# seamonster_buffered3.net
KiCad netlist of a schematic drawn in EAGLE
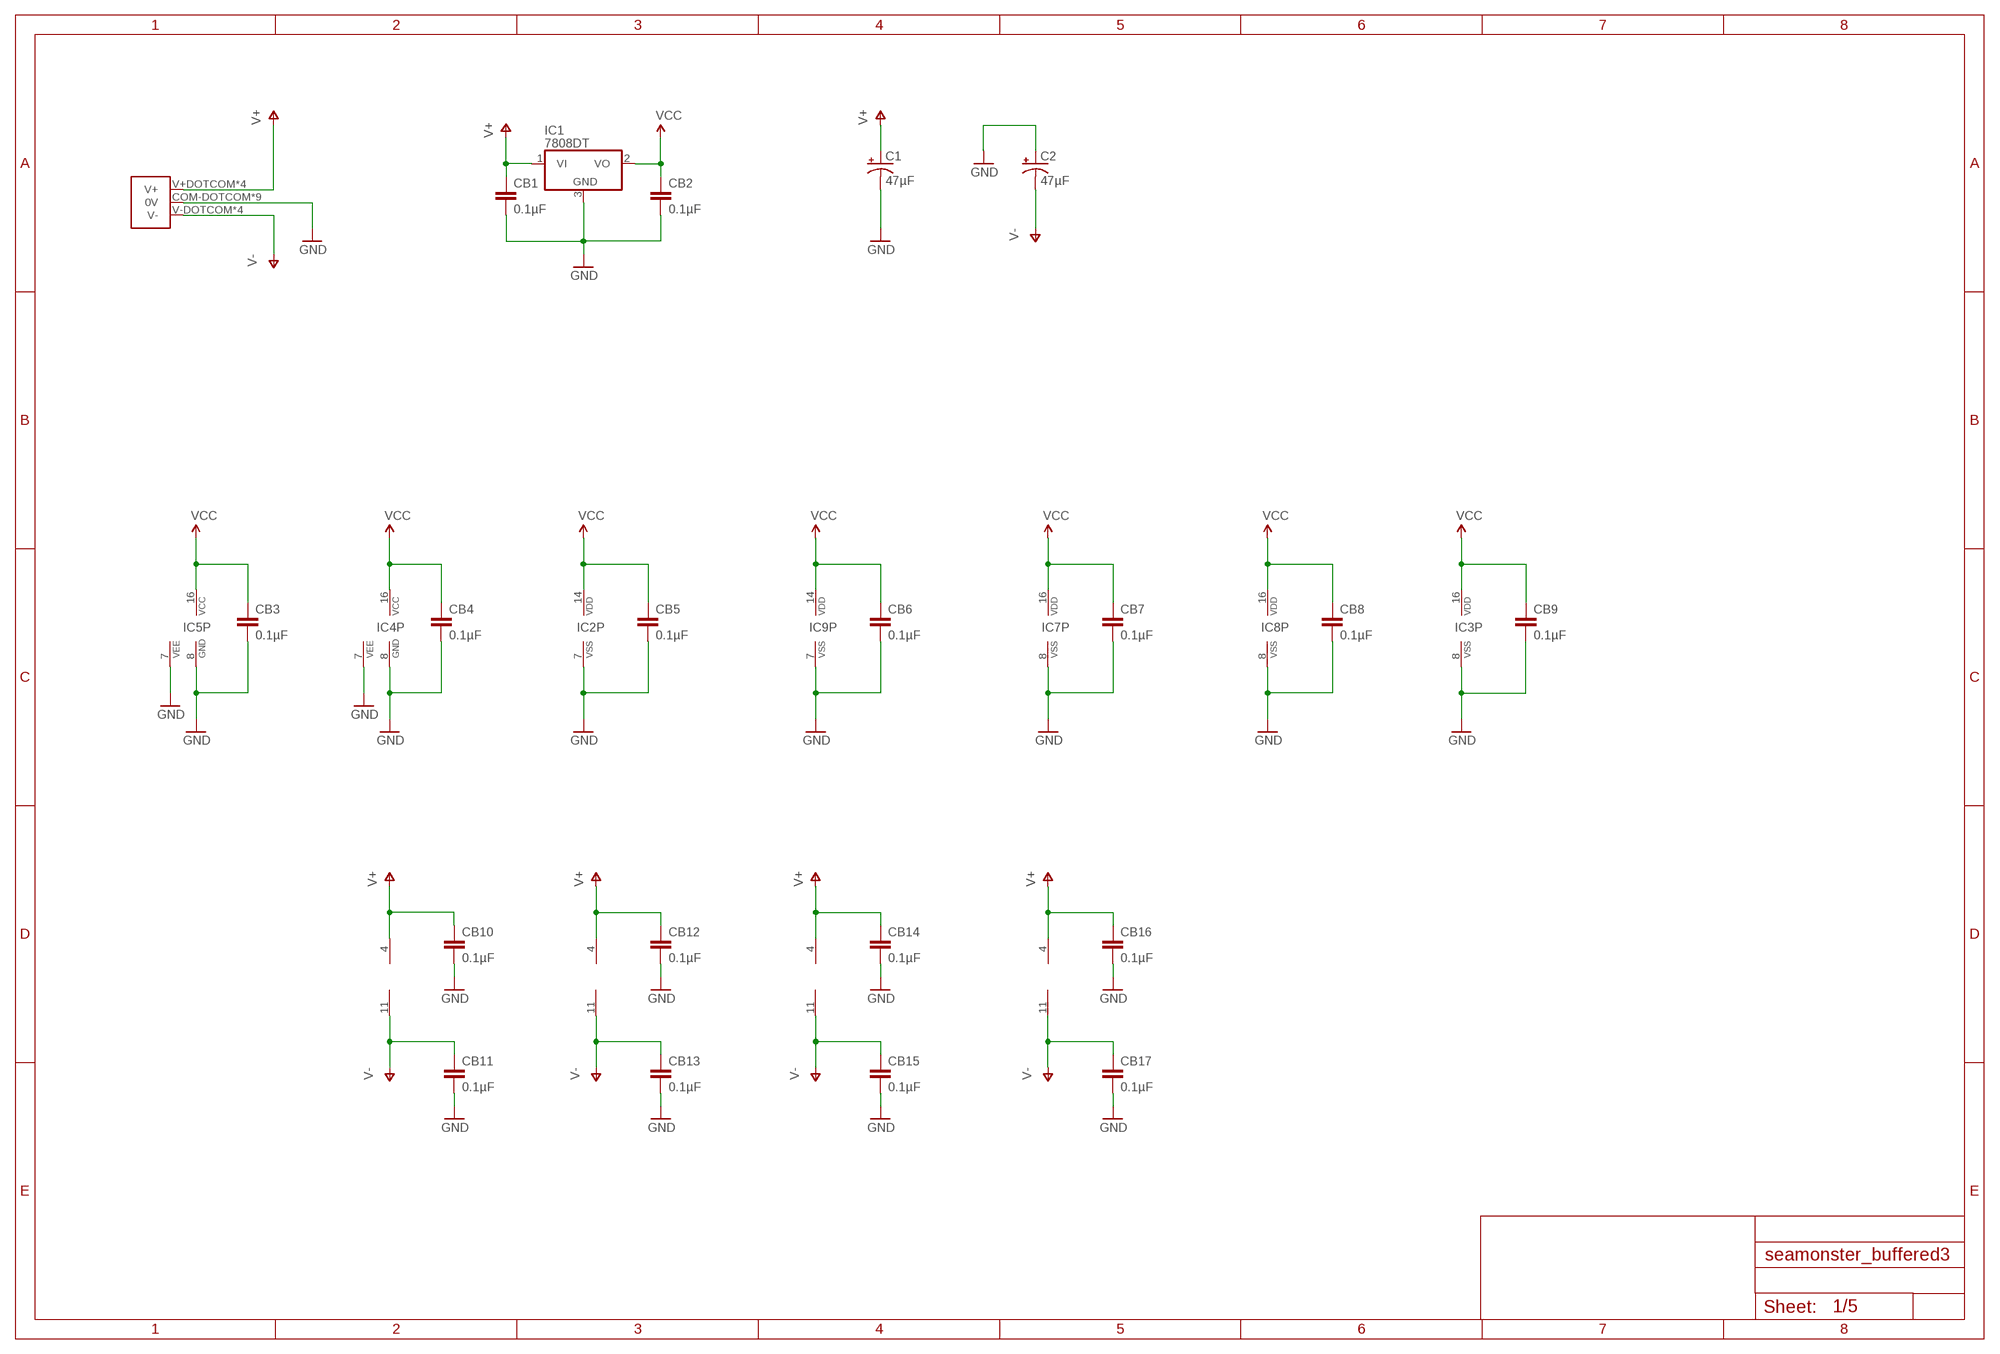
[diagram p0: schematic, sheet 1]
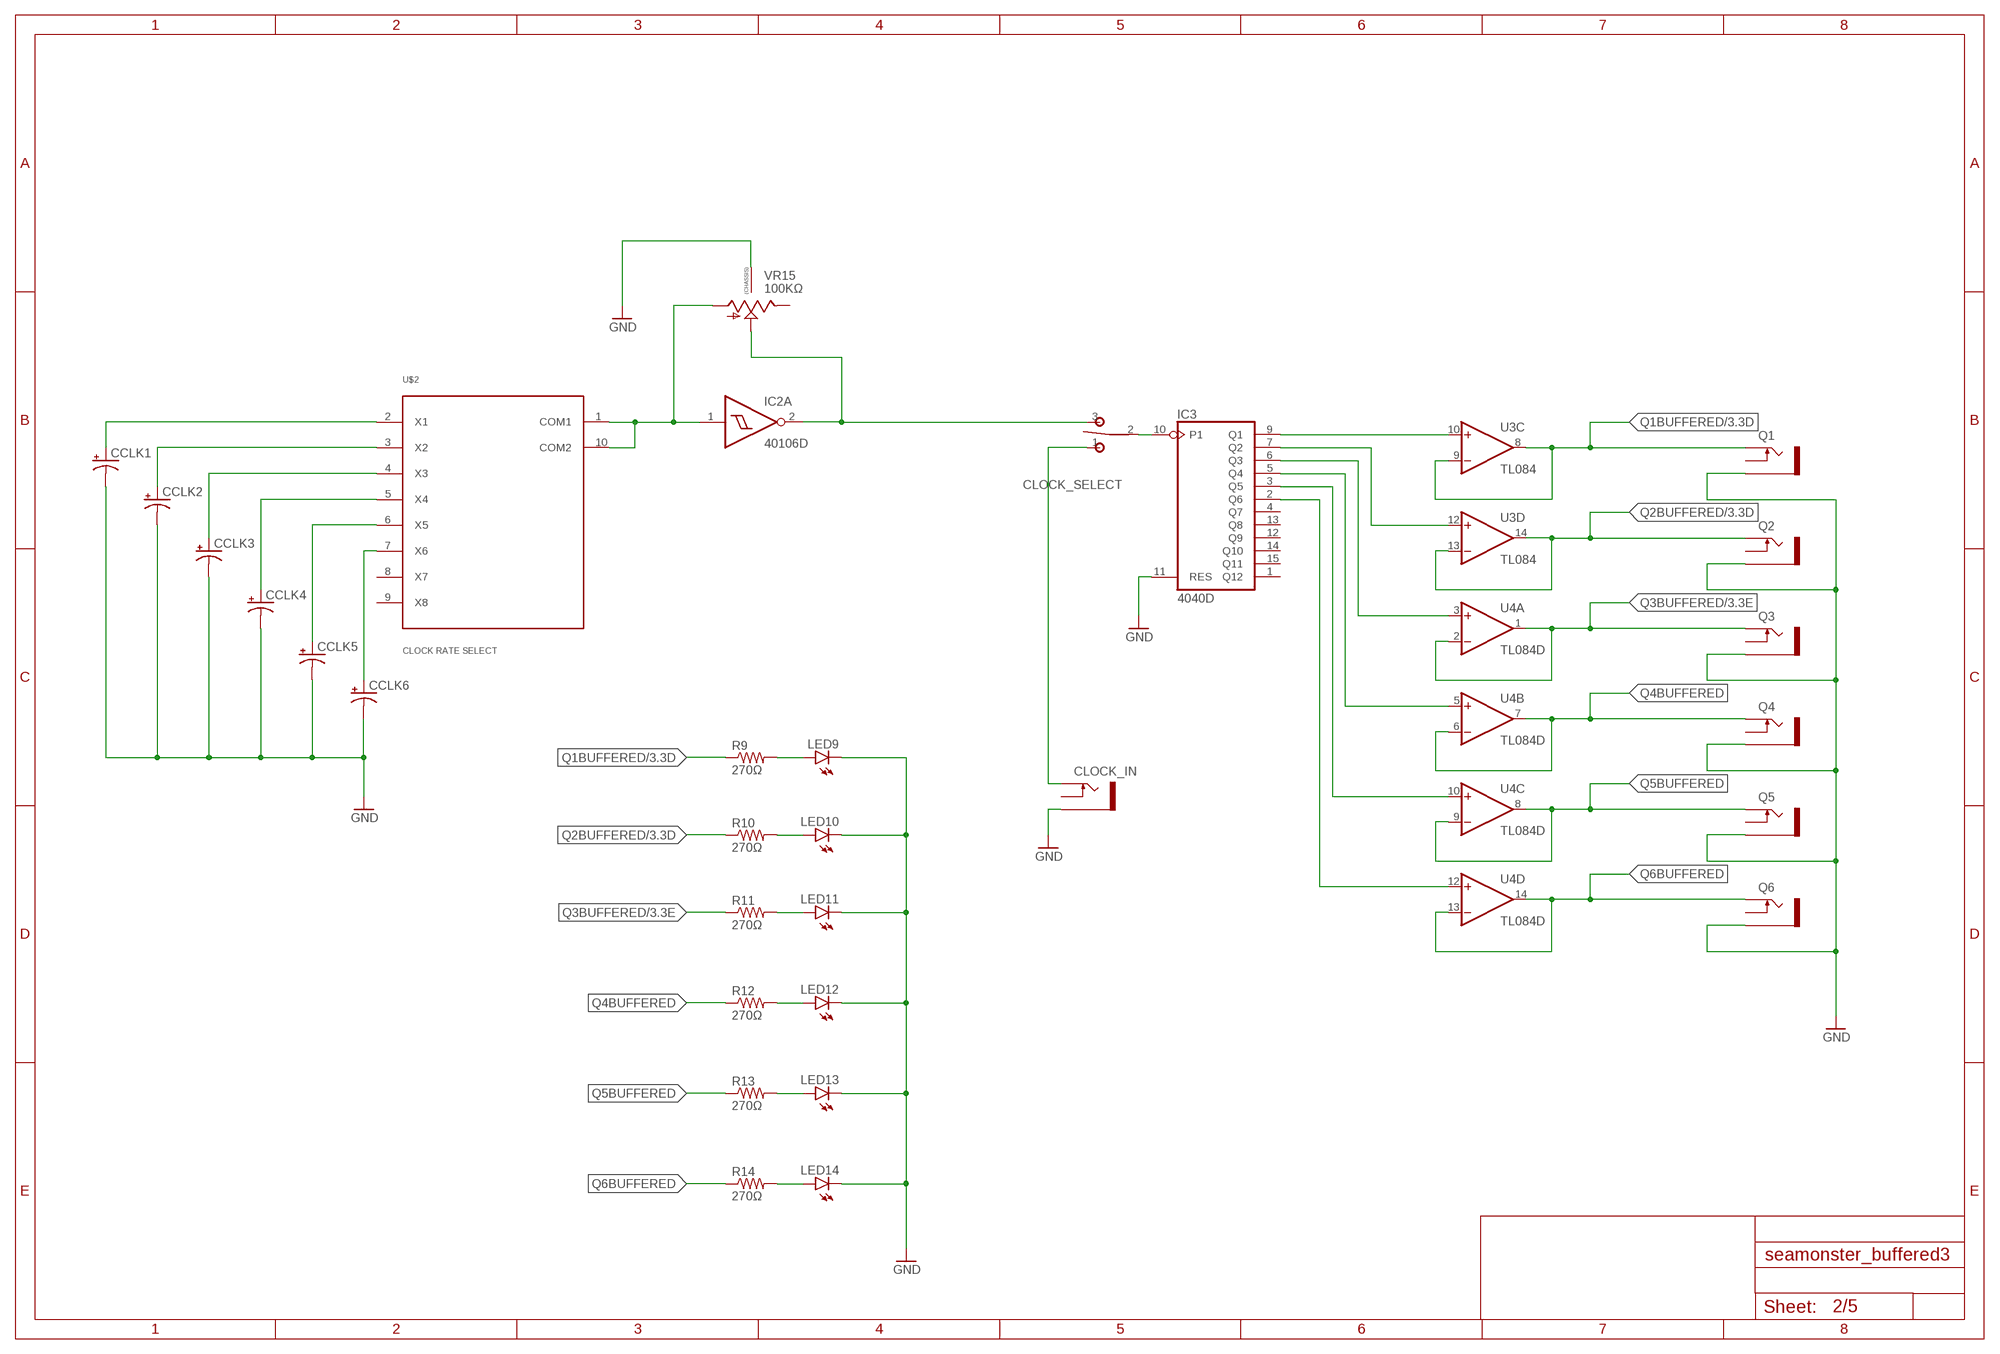
[diagram p1: schematic, sheet 2]
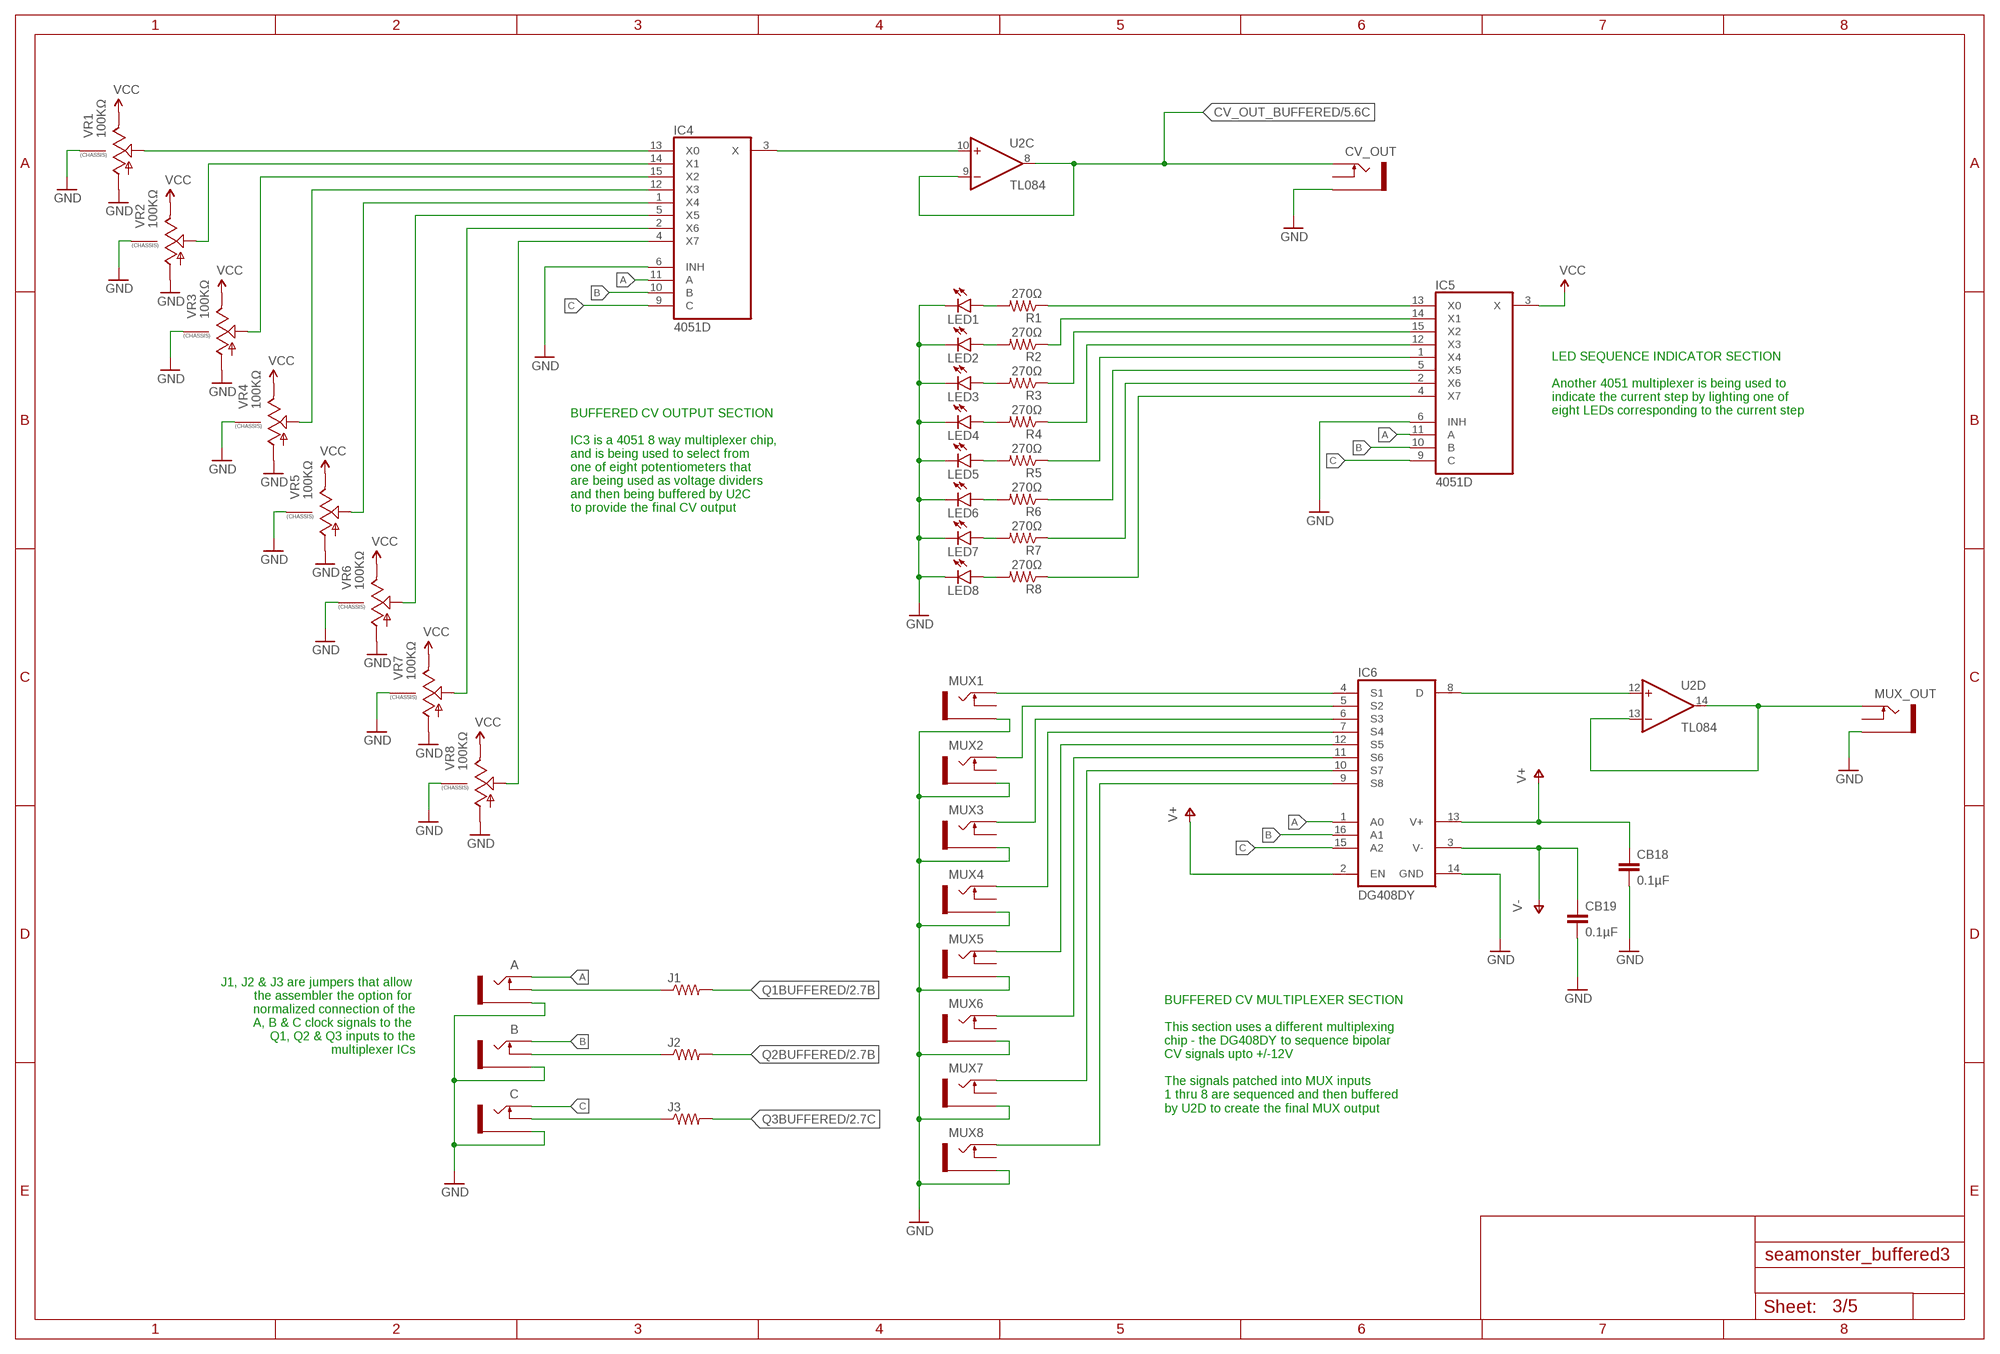
[diagram p2: schematic, sheet 3]
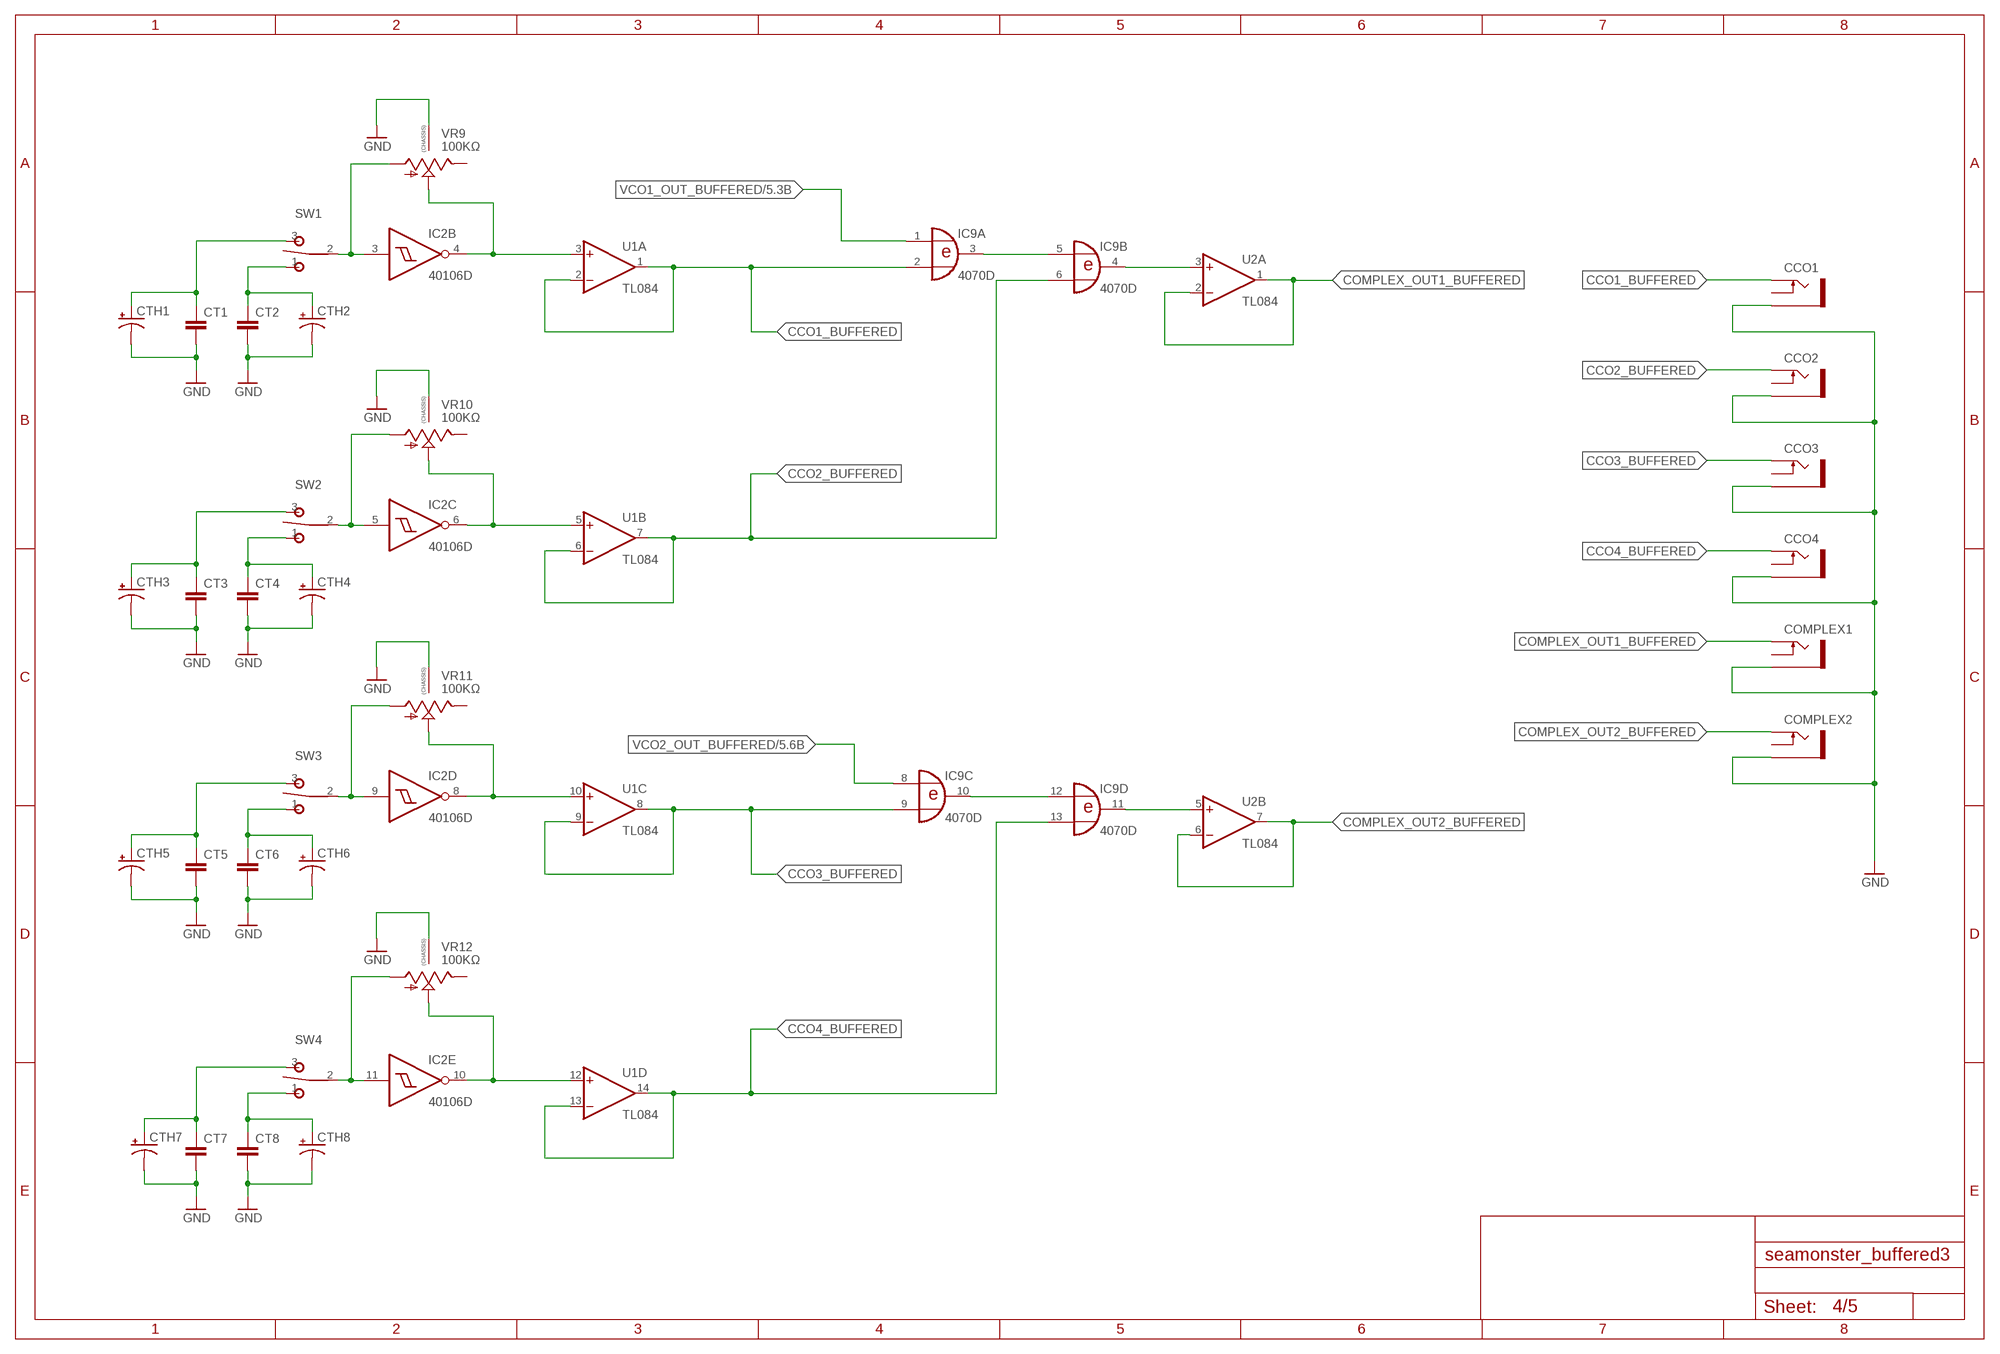
[diagram p3: schematic, sheet 4]
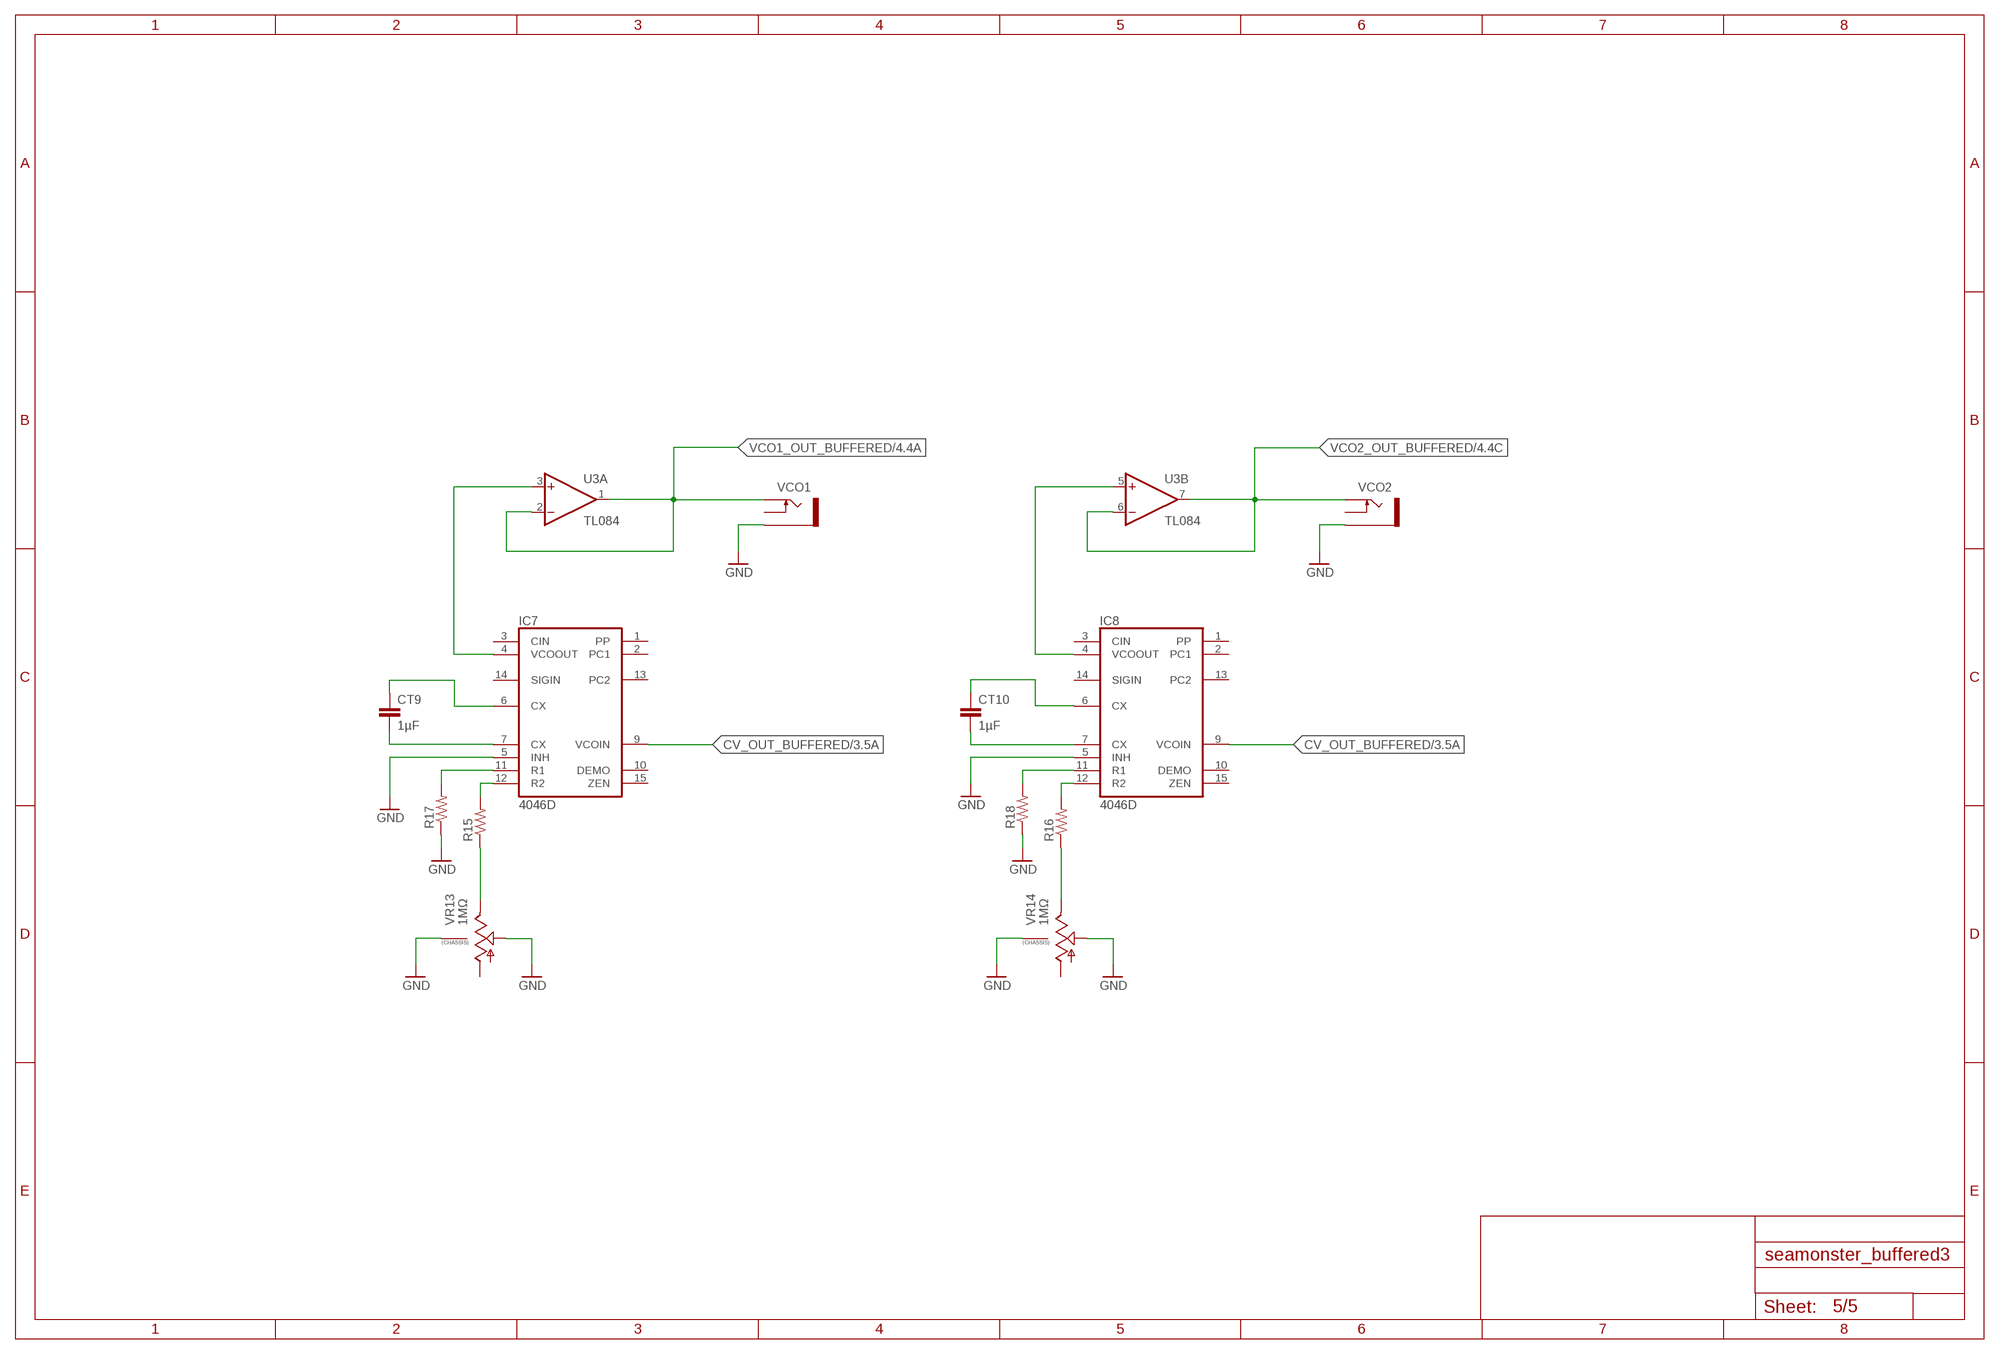
[diagram p4: schematic, sheet 5]

(export (version "E")
  (design (tool "Eeschema 10.0.6"))
  (components
    (comp (ref "A")
      (value "THONKICONNNEW")
      (footprint "eagle-import:WQP-PJ301M-12_JACK")
      (libsource (lib "eagle-import") (part "THONKICONNNEW"))
    )
    (comp (ref "B")
      (value "THONKICONNNEW")
      (footprint "eagle-import:WQP-PJ301M-12_JACK")
      (libsource (lib "eagle-import") (part "THONKICONNNEW"))
    )
    (comp (ref "C")
      (value "THONKICONNNEW")
      (footprint "eagle-import:WQP-PJ301M-12_JACK")
      (libsource (lib "eagle-import") (part "THONKICONNNEW"))
    )
    (comp (ref "CB18")
      (value "0.1µF")
      (footprint "eagle-import:0805")
      (libsource (lib "eagle-import") (part "CAP0805"))
    )
    (comp (ref "CB19")
      (value "0.1µF")
      (footprint "eagle-import:0805")
      (libsource (lib "eagle-import") (part "CAP0805"))
    )
    (comp (ref "CV_OUT")
      (value "THONKICONNNEW")
      (footprint "eagle-import:WQP-PJ301M-12_JACK")
      (libsource (lib "eagle-import") (part "THONKICONNNEW"))
    )
    (comp (ref "IC4")
      (value "4051D")
      (footprint "eagle-import:SO16")
      (libsource (lib "eagle-import") (part "4051D"))
    )
    (comp (ref "IC5")
      (value "4051D")
      (footprint "eagle-import:SO16")
      (libsource (lib "eagle-import") (part "4051D"))
    )
    (comp (ref "IC6")
      (value "DG408DY")
      (footprint "eagle-import:SO16")
      (fields (field (name "MPN") "DG408DY+T"))
      (libsource (lib "eagle-import") (part "DG408DY"))
    )
    (comp (ref "J1")
      (value "RESISTOR0805-RES")
      (footprint "eagle-import:0805")
      (libsource (lib "eagle-import") (part "RESISTOR0805-RES"))
    )
    (comp (ref "J2")
      (value "RESISTOR0805-RES")
      (footprint "eagle-import:0805")
      (libsource (lib "eagle-import") (part "RESISTOR0805-RES"))
    )
    (comp (ref "J3")
      (value "RESISTOR0805-RES")
      (footprint "eagle-import:0805")
      (libsource (lib "eagle-import") (part "RESISTOR0805-RES"))
    )
    (comp (ref "LED1")
      (value "LED3MM")
      (footprint "eagle-import:LED3MM")
      (libsource (lib "eagle-import") (part "LED3MM"))
    )
    (comp (ref "LED2")
      (value "LED3MM")
      (footprint "eagle-import:LED3MM")
      (libsource (lib "eagle-import") (part "LED3MM"))
    )
    (comp (ref "LED3")
      (value "LED3MM")
      (footprint "eagle-import:LED3MM")
      (libsource (lib "eagle-import") (part "LED3MM"))
    )
    (comp (ref "LED4")
      (value "LED3MM")
      (footprint "eagle-import:LED3MM")
      (libsource (lib "eagle-import") (part "LED3MM"))
    )
    (comp (ref "LED5")
      (value "LED3MM")
      (footprint "eagle-import:LED3MM")
      (libsource (lib "eagle-import") (part "LED3MM"))
    )
    (comp (ref "LED6")
      (value "LED3MM")
      (footprint "eagle-import:LED3MM")
      (libsource (lib "eagle-import") (part "LED3MM"))
    )
    (comp (ref "LED7")
      (value "LED3MM")
      (footprint "eagle-import:LED3MM")
      (libsource (lib "eagle-import") (part "LED3MM"))
    )
    (comp (ref "LED8")
      (value "LED3MM")
      (footprint "eagle-import:LED3MM")
      (libsource (lib "eagle-import") (part "LED3MM"))
    )
    (comp (ref "MUX1")
      (value "THONKICONNNEW")
      (footprint "eagle-import:WQP-PJ301M-12_JACK")
      (libsource (lib "eagle-import") (part "THONKICONNNEW"))
    )
    (comp (ref "MUX2")
      (value "THONKICONNNEW")
      (footprint "eagle-import:WQP-PJ301M-12_JACK")
      (libsource (lib "eagle-import") (part "THONKICONNNEW"))
    )
    (comp (ref "MUX3")
      (value "THONKICONNNEW")
      (footprint "eagle-import:WQP-PJ301M-12_JACK")
      (libsource (lib "eagle-import") (part "THONKICONNNEW"))
    )
    (comp (ref "MUX4")
      (value "THONKICONNNEW")
      (footprint "eagle-import:WQP-PJ301M-12_JACK")
      (libsource (lib "eagle-import") (part "THONKICONNNEW"))
    )
    (comp (ref "MUX5")
      (value "THONKICONNNEW")
      (footprint "eagle-import:WQP-PJ301M-12_JACK")
      (libsource (lib "eagle-import") (part "THONKICONNNEW"))
    )
    (comp (ref "MUX6")
      (value "THONKICONNNEW")
      (footprint "eagle-import:WQP-PJ301M-12_JACK")
      (libsource (lib "eagle-import") (part "THONKICONNNEW"))
    )
    (comp (ref "MUX7")
      (value "THONKICONNNEW")
      (footprint "eagle-import:WQP-PJ301M-12_JACK")
      (libsource (lib "eagle-import") (part "THONKICONNNEW"))
    )
    (comp (ref "MUX8")
      (value "THONKICONNNEW")
      (footprint "eagle-import:WQP-PJ301M-12_JACK")
      (libsource (lib "eagle-import") (part "THONKICONNNEW"))
    )
    (comp (ref "MUX_OUT")
      (value "THONKICONNNEW")
      (footprint "eagle-import:WQP-PJ301M-12_JACK")
      (libsource (lib "eagle-import") (part "THONKICONNNEW"))
    )
    (comp (ref "R1")
      (value "270Ω")
      (footprint "eagle-import:0805")
      (libsource (lib "eagle-import") (part "RESISTOR0805-RES"))
    )
    (comp (ref "R2")
      (value "270Ω")
      (footprint "eagle-import:0805")
      (libsource (lib "eagle-import") (part "RESISTOR0805-RES"))
    )
    (comp (ref "R3")
      (value "270Ω")
      (footprint "eagle-import:0805")
      (libsource (lib "eagle-import") (part "RESISTOR0805-RES"))
    )
    (comp (ref "R4")
      (value "270Ω")
      (footprint "eagle-import:0805")
      (libsource (lib "eagle-import") (part "RESISTOR0805-RES"))
    )
    (comp (ref "R5")
      (value "270Ω")
      (footprint "eagle-import:0805")
      (libsource (lib "eagle-import") (part "RESISTOR0805-RES"))
    )
    (comp (ref "R6")
      (value "270Ω")
      (footprint "eagle-import:0805")
      (libsource (lib "eagle-import") (part "RESISTOR0805-RES"))
    )
    (comp (ref "R7")
      (value "270Ω")
      (footprint "eagle-import:0805")
      (libsource (lib "eagle-import") (part "RESISTOR0805-RES"))
    )
    (comp (ref "R8")
      (value "270Ω")
      (footprint "eagle-import:0805")
      (libsource (lib "eagle-import") (part "RESISTOR0805-RES"))
    )
    (comp (ref "U2")
      (value "TL084")
      (footprint "eagle-import:SO14")
      (libsource (lib "eagle-import") (part "TL074_SMD"))
    )
    (comp (ref "VR1")
      (value "100KΩ")
      (footprint "eagle-import:9MM_SNAP-IN_POT")
      (libsource (lib "eagle-import") (part "9MM_SNAP-IN_POT_CHASSIS"))
    )
    (comp (ref "VR2")
      (value "100KΩ")
      (footprint "eagle-import:9MM_SNAP-IN_POT")
      (libsource (lib "eagle-import") (part "9MM_SNAP-IN_POT_CHASSIS"))
    )
    (comp (ref "VR3")
      (value "100KΩ")
      (footprint "eagle-import:9MM_SNAP-IN_POT")
      (libsource (lib "eagle-import") (part "9MM_SNAP-IN_POT_CHASSIS"))
    )
    (comp (ref "VR4")
      (value "100KΩ")
      (footprint "eagle-import:9MM_SNAP-IN_POT")
      (libsource (lib "eagle-import") (part "9MM_SNAP-IN_POT_CHASSIS"))
    )
    (comp (ref "VR5")
      (value "100KΩ")
      (footprint "eagle-import:9MM_SNAP-IN_POT")
      (libsource (lib "eagle-import") (part "9MM_SNAP-IN_POT_CHASSIS"))
    )
    (comp (ref "VR6")
      (value "100KΩ")
      (footprint "eagle-import:9MM_SNAP-IN_POT")
      (libsource (lib "eagle-import") (part "9MM_SNAP-IN_POT_CHASSIS"))
    )
    (comp (ref "VR7")
      (value "100KΩ")
      (footprint "eagle-import:9MM_SNAP-IN_POT")
      (libsource (lib "eagle-import") (part "9MM_SNAP-IN_POT_CHASSIS"))
    )
    (comp (ref "VR8")
      (value "100KΩ")
      (footprint "eagle-import:9MM_SNAP-IN_POT")
      (libsource (lib "eagle-import") (part "9MM_SNAP-IN_POT_CHASSIS"))
    )
    (comp (ref "CCO1")
      (value "THONKICONNNEW")
      (footprint "eagle-import:WQP-PJ301M-12_JACK")
      (libsource (lib "eagle-import") (part "THONKICONNNEW"))
    )
    (comp (ref "CCO2")
      (value "THONKICONNNEW")
      (footprint "eagle-import:WQP-PJ301M-12_JACK")
      (libsource (lib "eagle-import") (part "THONKICONNNEW"))
    )
    (comp (ref "CCO3")
      (value "THONKICONNNEW")
      (footprint "eagle-import:WQP-PJ301M-12_JACK")
      (libsource (lib "eagle-import") (part "THONKICONNNEW"))
    )
    (comp (ref "CCO4")
      (value "THONKICONNNEW")
      (footprint "eagle-import:WQP-PJ301M-12_JACK")
      (libsource (lib "eagle-import") (part "THONKICONNNEW"))
    )
    (comp (ref "COMPLEX1")
      (value "THONKICONNNEW")
      (footprint "eagle-import:WQP-PJ301M-12_JACK")
      (libsource (lib "eagle-import") (part "THONKICONNNEW"))
    )
    (comp (ref "COMPLEX2")
      (value "THONKICONNNEW")
      (footprint "eagle-import:WQP-PJ301M-12_JACK")
      (libsource (lib "eagle-import") (part "THONKICONNNEW"))
    )
    (comp (ref "CT1")
      (value "CAP0805")
      (footprint "eagle-import:0805")
      (libsource (lib "eagle-import") (part "CAP0805"))
    )
    (comp (ref "CT2")
      (value "CAP0805")
      (footprint "eagle-import:0805")
      (libsource (lib "eagle-import") (part "CAP0805"))
    )
    (comp (ref "CT3")
      (value "CAP0805")
      (footprint "eagle-import:0805")
      (libsource (lib "eagle-import") (part "CAP0805"))
    )
    (comp (ref "CT4")
      (value "CAP0805")
      (footprint "eagle-import:0805")
      (libsource (lib "eagle-import") (part "CAP0805"))
    )
    (comp (ref "CT5")
      (value "CAP0805")
      (footprint "eagle-import:0805")
      (libsource (lib "eagle-import") (part "CAP0805"))
    )
    (comp (ref "CT6")
      (value "CAP0805")
      (footprint "eagle-import:0805")
      (libsource (lib "eagle-import") (part "CAP0805"))
    )
    (comp (ref "CT7")
      (value "CAP0805")
      (footprint "eagle-import:0805")
      (libsource (lib "eagle-import") (part "CAP0805"))
    )
    (comp (ref "CT8")
      (value "CAP0805")
      (footprint "eagle-import:0805")
      (libsource (lib "eagle-import") (part "CAP0805"))
    )
    (comp (ref "CTH1")
      (value "CAP_POLPTH2")
      (footprint "eagle-import:CPOL-RADIAL-10UF-25V")
      (libsource (lib "eagle-import") (part "CAP_POLPTH2"))
    )
    (comp (ref "CTH2")
      (value "CAP_POLPTH2")
      (footprint "eagle-import:CPOL-RADIAL-10UF-25V")
      (libsource (lib "eagle-import") (part "CAP_POLPTH2"))
    )
    (comp (ref "CTH3")
      (value "CAP_POLPTH2")
      (footprint "eagle-import:CPOL-RADIAL-10UF-25V")
      (libsource (lib "eagle-import") (part "CAP_POLPTH2"))
    )
    (comp (ref "CTH4")
      (value "CAP_POLPTH2")
      (footprint "eagle-import:CPOL-RADIAL-10UF-25V")
      (libsource (lib "eagle-import") (part "CAP_POLPTH2"))
    )
    (comp (ref "CTH5")
      (value "CAP_POLPTH2")
      (footprint "eagle-import:CPOL-RADIAL-10UF-25V")
      (libsource (lib "eagle-import") (part "CAP_POLPTH2"))
    )
    (comp (ref "CTH6")
      (value "CAP_POLPTH2")
      (footprint "eagle-import:CPOL-RADIAL-10UF-25V")
      (libsource (lib "eagle-import") (part "CAP_POLPTH2"))
    )
    (comp (ref "CTH7")
      (value "CAP_POLPTH2")
      (footprint "eagle-import:CPOL-RADIAL-10UF-25V")
      (libsource (lib "eagle-import") (part "CAP_POLPTH2"))
    )
    (comp (ref "CTH8")
      (value "CAP_POLPTH2")
      (footprint "eagle-import:CPOL-RADIAL-10UF-25V")
      (libsource (lib "eagle-import") (part "CAP_POLPTH2"))
    )
    (comp (ref "IC2")
      (value "40106D")
      (footprint "eagle-import:SO14")
      (libsource (lib "eagle-import") (part "40106D"))
    )
    (comp (ref "IC9")
      (value "4070D")
      (footprint "eagle-import:SO14")
      (libsource (lib "eagle-import") (part "4070D"))
    )
    (comp (ref "SW1")
      (value "SPDT ON-ON")
      (footprint "eagle-import:M9040P")
      (libsource (lib "eagle-import") (part "T-80-T-SPDT-ON-OFF-ON"))
    )
    (comp (ref "SW2")
      (value "SPDT ON-ON")
      (footprint "eagle-import:M9040P")
      (libsource (lib "eagle-import") (part "T-80-T-SPDT-ON-OFF-ON"))
    )
    (comp (ref "SW3")
      (value "SPDT ON-ON")
      (footprint "eagle-import:M9040P")
      (libsource (lib "eagle-import") (part "T-80-T-SPDT-ON-OFF-ON"))
    )
    (comp (ref "SW4")
      (value "SPDT ON-ON")
      (footprint "eagle-import:M9040P")
      (libsource (lib "eagle-import") (part "T-80-T-SPDT-ON-OFF-ON"))
    )
    (comp (ref "U1")
      (value "TL084")
      (footprint "eagle-import:SO14")
      (libsource (lib "eagle-import") (part "TL074_SMD"))
    )
    (comp (ref "VR9")
      (value "100KΩ")
      (footprint "eagle-import:9MM_SNAP-IN_POT")
      (libsource (lib "eagle-import") (part "9MM_SNAP-IN_POT_CHASSIS"))
    )
    (comp (ref "VR10")
      (value "100KΩ")
      (footprint "eagle-import:9MM_SNAP-IN_POT")
      (libsource (lib "eagle-import") (part "9MM_SNAP-IN_POT_CHASSIS"))
    )
    (comp (ref "VR11")
      (value "100KΩ")
      (footprint "eagle-import:9MM_SNAP-IN_POT")
      (libsource (lib "eagle-import") (part "9MM_SNAP-IN_POT_CHASSIS"))
    )
    (comp (ref "VR12")
      (value "100KΩ")
      (footprint "eagle-import:9MM_SNAP-IN_POT")
      (libsource (lib "eagle-import") (part "9MM_SNAP-IN_POT_CHASSIS"))
    )
    (comp (ref "CCLK1")
      (value "10UF-25V-20%(PTH)")
      (footprint "eagle-import:CPOL-RADIAL-10UF-25V")
      (libsource (lib "eagle-import") (part "10UF-25V-20%(PTH)"))
    )
    (comp (ref "CCLK2")
      (value "10UF-25V-20%(PTH)")
      (footprint "eagle-import:CPOL-RADIAL-10UF-25V")
      (libsource (lib "eagle-import") (part "10UF-25V-20%(PTH)"))
    )
    (comp (ref "CCLK3")
      (value "10UF-25V-20%(PTH)")
      (footprint "eagle-import:CPOL-RADIAL-10UF-25V")
      (libsource (lib "eagle-import") (part "10UF-25V-20%(PTH)"))
    )
    (comp (ref "CCLK4")
      (value "10UF-25V-20%(PTH)")
      (footprint "eagle-import:CPOL-RADIAL-10UF-25V")
      (libsource (lib "eagle-import") (part "10UF-25V-20%(PTH)"))
    )
    (comp (ref "CCLK5")
      (value "10UF-25V-20%(PTH)")
      (footprint "eagle-import:CPOL-RADIAL-10UF-25V")
      (libsource (lib "eagle-import") (part "10UF-25V-20%(PTH)"))
    )
    (comp (ref "CCLK6")
      (value "10UF-25V-20%(PTH)")
      (footprint "eagle-import:CPOL-RADIAL-10UF-25V")
      (libsource (lib "eagle-import") (part "10UF-25V-20%(PTH)"))
    )
    (comp (ref "CLOCK_IN")
      (value "THONKICONNNEW")
      (footprint "eagle-import:WQP-PJ301M-12_JACK")
      (libsource (lib "eagle-import") (part "THONKICONNNEW"))
    )
    (comp (ref "CLOCK_SELECT")
      (value "SPDT ON-ON")
      (footprint "eagle-import:M9040P")
      (libsource (lib "eagle-import") (part "T-80-T-SPDT-ON-OFF-ON"))
    )
    (comp (ref "IC3")
      (value "4040D")
      (footprint "eagle-import:SO16")
      (libsource (lib "eagle-import") (part "4040D"))
    )
    (comp (ref "LED9")
      (value "LED3MM")
      (footprint "eagle-import:LED3MM")
      (libsource (lib "eagle-import") (part "LED3MM"))
    )
    (comp (ref "LED10")
      (value "LED3MM")
      (footprint "eagle-import:LED3MM")
      (libsource (lib "eagle-import") (part "LED3MM"))
    )
    (comp (ref "LED11")
      (value "LED3MM")
      (footprint "eagle-import:LED3MM")
      (libsource (lib "eagle-import") (part "LED3MM"))
    )
    (comp (ref "LED12")
      (value "LED3MM")
      (footprint "eagle-import:LED3MM")
      (libsource (lib "eagle-import") (part "LED3MM"))
    )
    (comp (ref "LED13")
      (value "LED3MM")
      (footprint "eagle-import:LED3MM")
      (libsource (lib "eagle-import") (part "LED3MM"))
    )
    (comp (ref "LED14")
      (value "LED3MM")
      (footprint "eagle-import:LED3MM")
      (libsource (lib "eagle-import") (part "LED3MM"))
    )
    (comp (ref "Q1")
      (value "THONKICONNNEW")
      (footprint "eagle-import:WQP-PJ301M-12_JACK")
      (libsource (lib "eagle-import") (part "THONKICONNNEW"))
    )
    (comp (ref "Q2")
      (value "THONKICONNNEW")
      (footprint "eagle-import:WQP-PJ301M-12_JACK")
      (libsource (lib "eagle-import") (part "THONKICONNNEW"))
    )
    (comp (ref "Q3")
      (value "THONKICONNNEW")
      (footprint "eagle-import:WQP-PJ301M-12_JACK")
      (libsource (lib "eagle-import") (part "THONKICONNNEW"))
    )
    (comp (ref "Q4")
      (value "THONKICONNNEW")
      (footprint "eagle-import:WQP-PJ301M-12_JACK")
      (libsource (lib "eagle-import") (part "THONKICONNNEW"))
    )
    (comp (ref "Q5")
      (value "THONKICONNNEW")
      (footprint "eagle-import:WQP-PJ301M-12_JACK")
      (libsource (lib "eagle-import") (part "THONKICONNNEW"))
    )
    (comp (ref "Q6")
      (value "THONKICONNNEW")
      (footprint "eagle-import:WQP-PJ301M-12_JACK")
      (libsource (lib "eagle-import") (part "THONKICONNNEW"))
    )
    (comp (ref "R9")
      (value "270Ω")
      (footprint "eagle-import:0805")
      (libsource (lib "eagle-import") (part "RESISTOR0805-RES"))
    )
    (comp (ref "R10")
      (value "270Ω")
      (footprint "eagle-import:0805")
      (libsource (lib "eagle-import") (part "RESISTOR0805-RES"))
    )
    (comp (ref "R11")
      (value "270Ω")
      (footprint "eagle-import:0805")
      (libsource (lib "eagle-import") (part "RESISTOR0805-RES"))
    )
    (comp (ref "R12")
      (value "270Ω")
      (footprint "eagle-import:0805")
      (libsource (lib "eagle-import") (part "RESISTOR0805-RES"))
    )
    (comp (ref "R13")
      (value "270Ω")
      (footprint "eagle-import:0805")
      (libsource (lib "eagle-import") (part "RESISTOR0805-RES"))
    )
    (comp (ref "R14")
      (value "270Ω")
      (footprint "eagle-import:0805")
      (libsource (lib "eagle-import") (part "RESISTOR0805-RES"))
    )
    (comp (ref "U$2")
      (value "CLOCK RATE SELECT")
      (footprint "eagle-import:ALPHA_SR1712F")
      (libsource (lib "eagle-import") (part "ALPHA_ROTARY_SWITCH"))
    )
    (comp (ref "U3")
      (value "TL084")
      (footprint "eagle-import:SO14")
      (libsource (lib "eagle-import") (part "TL074_SMD"))
    )
    (comp (ref "U4")
      (value "TL084D")
      (footprint "eagle-import:SO14")
      (libsource (lib "eagle-import") (part "TL084D"))
    )
    (comp (ref "VR15")
      (value "100KΩ")
      (footprint "eagle-import:9MM_SNAP-IN_POT")
      (libsource (lib "eagle-import") (part "9MM_SNAP-IN_POT_CHASSIS"))
    )
    (comp (ref "CT9")
      (value "1µF")
      (footprint "eagle-import:0805")
      (libsource (lib "eagle-import") (part "CAP0805"))
    )
    (comp (ref "CT10")
      (value "1µF")
      (footprint "eagle-import:0805")
      (libsource (lib "eagle-import") (part "CAP0805"))
    )
    (comp (ref "IC7")
      (value "4046D")
      (footprint "eagle-import:SO16")
      (libsource (lib "eagle-import") (part "4046D"))
    )
    (comp (ref "IC8")
      (value "4046D")
      (footprint "eagle-import:SO16")
      (libsource (lib "eagle-import") (part "4046D"))
    )
    (comp (ref "R15")
      (value "RESISTOR0805-RES")
      (footprint "eagle-import:0805")
      (libsource (lib "eagle-import") (part "RESISTOR0805-RES"))
    )
    (comp (ref "R16")
      (value "RESISTOR0805-RES")
      (footprint "eagle-import:0805")
      (libsource (lib "eagle-import") (part "RESISTOR0805-RES"))
    )
    (comp (ref "R17")
      (value "RESISTOR0805-RES")
      (footprint "eagle-import:0805")
      (libsource (lib "eagle-import") (part "RESISTOR0805-RES"))
    )
    (comp (ref "R18")
      (value "RESISTOR0805-RES")
      (footprint "eagle-import:0805")
      (libsource (lib "eagle-import") (part "RESISTOR0805-RES"))
    )
    (comp (ref "VCO1")
      (value "THONKICONNNEW")
      (footprint "eagle-import:WQP-PJ301M-12_JACK")
      (libsource (lib "eagle-import") (part "THONKICONNNEW"))
    )
    (comp (ref "VCO2")
      (value "THONKICONNNEW")
      (footprint "eagle-import:WQP-PJ301M-12_JACK")
      (libsource (lib "eagle-import") (part "THONKICONNNEW"))
    )
    (comp (ref "VR13")
      (value "1MΩ")
      (footprint "eagle-import:9MM_SNAP-IN_POT")
      (libsource (lib "eagle-import") (part "9MM_SNAP-IN_POT_CHASSIS"))
    )
    (comp (ref "VR14")
      (value "1MΩ")
      (footprint "eagle-import:9MM_SNAP-IN_POT")
      (libsource (lib "eagle-import") (part "9MM_SNAP-IN_POT_CHASSIS"))
    )
    (comp (ref "C1")
      (value "47µF")
      (footprint "eagle-import:CPOL-RADIAL-10UF-25V")
      (libsource (lib "eagle-import") (part "CAP_POLPTH2"))
    )
    (comp (ref "C2")
      (value "47µF")
      (footprint "eagle-import:CPOL-RADIAL-10UF-25V")
      (libsource (lib "eagle-import") (part "CAP_POLPTH2"))
    )
    (comp (ref "CB1")
      (value "0.1µF")
      (footprint "eagle-import:0805")
      (libsource (lib "eagle-import") (part "CAP0805"))
    )
    (comp (ref "CB2")
      (value "0.1µF")
      (footprint "eagle-import:0805")
      (libsource (lib "eagle-import") (part "CAP0805"))
    )
    (comp (ref "CB3")
      (value "0.1µF")
      (footprint "eagle-import:0805")
      (libsource (lib "eagle-import") (part "CAP0805"))
    )
    (comp (ref "CB4")
      (value "0.1µF")
      (footprint "eagle-import:0805")
      (libsource (lib "eagle-import") (part "CAP0805"))
    )
    (comp (ref "CB5")
      (value "0.1µF")
      (footprint "eagle-import:0805")
      (libsource (lib "eagle-import") (part "CAP0805"))
    )
    (comp (ref "CB6")
      (value "0.1µF")
      (footprint "eagle-import:0805")
      (libsource (lib "eagle-import") (part "CAP0805"))
    )
    (comp (ref "CB7")
      (value "0.1µF")
      (footprint "eagle-import:0805")
      (libsource (lib "eagle-import") (part "CAP0805"))
    )
    (comp (ref "CB8")
      (value "0.1µF")
      (footprint "eagle-import:0805")
      (libsource (lib "eagle-import") (part "CAP0805"))
    )
    (comp (ref "CB9")
      (value "0.1µF")
      (footprint "eagle-import:0805")
      (libsource (lib "eagle-import") (part "CAP0805"))
    )
    (comp (ref "CB10")
      (value "0.1µF")
      (footprint "eagle-import:0805")
      (libsource (lib "eagle-import") (part "CAP0805"))
    )
    (comp (ref "CB11")
      (value "0.1µF")
      (footprint "eagle-import:0805")
      (libsource (lib "eagle-import") (part "CAP0805"))
    )
    (comp (ref "CB12")
      (value "0.1µF")
      (footprint "eagle-import:0805")
      (libsource (lib "eagle-import") (part "CAP0805"))
    )
    (comp (ref "CB13")
      (value "0.1µF")
      (footprint "eagle-import:0805")
      (libsource (lib "eagle-import") (part "CAP0805"))
    )
    (comp (ref "CB14")
      (value "0.1µF")
      (footprint "eagle-import:0805")
      (libsource (lib "eagle-import") (part "CAP0805"))
    )
    (comp (ref "CB15")
      (value "0.1µF")
      (footprint "eagle-import:0805")
      (libsource (lib "eagle-import") (part "CAP0805"))
    )
    (comp (ref "CB16")
      (value "0.1µF")
      (footprint "eagle-import:0805")
      (libsource (lib "eagle-import") (part "CAP0805"))
    )
    (comp (ref "CB17")
      (value "0.1µF")
      (footprint "eagle-import:0805")
      (libsource (lib "eagle-import") (part "CAP0805"))
    )
    (comp (ref "IC1")
      (value "7808DT")
      (footprint "eagle-import:TO252")
      (libsource (lib "eagle-import") (part "78DT08"))
    )
    (comp (ref "U$1")
      (value "COMBO_POWER")
      (footprint "eagle-import:COMBO_POWER")
      (libsource (lib "eagle-import") (part "COMBO_POWER"))
    )
  )
  (nets
    (net (code "1") (name "A") (class "Default")
      (node (ref "A") (pin "P$1_TIP") (pinfunction "TIP_P$1_TIP") (pintype "passive"))
      (node (ref "IC4") (pin "11") (pinfunction "A_11") (pintype "input"))
      (node (ref "IC5") (pin "11") (pinfunction "A_11") (pintype "input"))
      (node (ref "IC6") (pin "1") (pinfunction "A0_1") (pintype "input"))
    )
    (net (code "2") (name "B") (class "Default")
      (node (ref "B") (pin "P$1_TIP") (pinfunction "TIP_P$1_TIP") (pintype "passive"))
      (node (ref "IC4") (pin "10") (pinfunction "B_10") (pintype "input"))
      (node (ref "IC5") (pin "10") (pinfunction "B_10") (pintype "input"))
      (node (ref "IC6") (pin "16") (pinfunction "A1_16") (pintype "input"))
    )
    (net (code "3") (name "C") (class "Default")
      (node (ref "C") (pin "P$1_TIP") (pinfunction "TIP_P$1_TIP") (pintype "passive"))
      (node (ref "IC4") (pin "9") (pinfunction "C_9") (pintype "input"))
      (node (ref "IC5") (pin "9") (pinfunction "C_9") (pintype "input"))
      (node (ref "IC6") (pin "15") (pinfunction "A2_15") (pintype "input"))
    )
    (net (code "4") (name "CCO1_BUFFERED") (class "Default")
      (node (ref "CCO1") (pin "P$1_TIP") (pinfunction "TIP_P$1_TIP") (pintype "passive"))
      (node (ref "IC9") (pin "2") (pinfunction "I1_2") (pintype "input"))
      (node (ref "U1") (pin "1") (pinfunction "OUT_1") (pintype "output"))
      (node (ref "U1") (pin "2") (pinfunction "-IN_2") (pintype "input"))
    )
    (net (code "5") (name "CCO2_BUFFERED") (class "Default")
      (node (ref "CCO2") (pin "P$1_TIP") (pinfunction "TIP_P$1_TIP") (pintype "passive"))
      (node (ref "IC9") (pin "6") (pinfunction "I1_6") (pintype "input"))
      (node (ref "U1") (pin "6") (pinfunction "-IN_6") (pintype "input"))
      (node (ref "U1") (pin "7") (pinfunction "OUT_7") (pintype "output"))
    )
    (net (code "6") (name "CCO3_BUFFERED") (class "Default")
      (node (ref "CCO3") (pin "P$1_TIP") (pinfunction "TIP_P$1_TIP") (pintype "passive"))
      (node (ref "IC9") (pin "9") (pinfunction "I1_9") (pintype "input"))
      (node (ref "U1") (pin "8") (pinfunction "OUT_8") (pintype "output"))
      (node (ref "U1") (pin "9") (pinfunction "-IN_9") (pintype "input"))
    )
    (net (code "7") (name "CCO4_BUFFERED") (class "Default")
      (node (ref "CCO4") (pin "P$1_TIP") (pinfunction "TIP_P$1_TIP") (pintype "passive"))
      (node (ref "IC9") (pin "13") (pinfunction "I1_13") (pintype "input"))
      (node (ref "U1") (pin "13") (pinfunction "-IN_13") (pintype "input"))
      (node (ref "U1") (pin "14") (pinfunction "OUT_14") (pintype "output"))
    )
    (net (code "8") (name "COMPLEX_OUT1_BUFFERED") (class "Default")
      (node (ref "COMPLEX1") (pin "P$1_TIP") (pinfunction "TIP_P$1_TIP") (pintype "passive"))
      (node (ref "U2") (pin "1") (pinfunction "OUT_1") (pintype "output"))
      (node (ref "U2") (pin "2") (pinfunction "-IN_2") (pintype "input"))
    )
    (net (code "9") (name "COMPLEX_OUT2_BUFFERED") (class "Default")
      (node (ref "COMPLEX2") (pin "P$1_TIP") (pinfunction "TIP_P$1_TIP") (pintype "passive"))
      (node (ref "U2") (pin "6") (pinfunction "-IN_6") (pintype "input"))
      (node (ref "U2") (pin "7") (pinfunction "OUT_7") (pintype "output"))
    )
    (net (code "10") (name "CV_OUT_BUFFERED") (class "Default")
      (node (ref "CV_OUT") (pin "P$1_TIP") (pinfunction "TIP_P$1_TIP") (pintype "passive"))
      (node (ref "IC7") (pin "9") (pinfunction "VCOIN_9") (pintype "input"))
      (node (ref "IC8") (pin "9") (pinfunction "VCOIN_9") (pintype "input"))
      (node (ref "U2") (pin "8") (pinfunction "OUT_8") (pintype "output"))
      (node (ref "U2") (pin "9") (pinfunction "-IN_9") (pintype "input"))
    )
    (net (code "11") (name "GND") (class "Default")
      (node (ref "A") (pin "P$3_SLEEVE") (pinfunction "SLEEVE_P$3_SLEEVE") (pintype "passive"))
      (node (ref "B") (pin "P$3_SLEEVE") (pinfunction "SLEEVE_P$3_SLEEVE") (pintype "passive"))
      (node (ref "C") (pin "P$3_SLEEVE") (pinfunction "SLEEVE_P$3_SLEEVE") (pintype "passive"))
      (node (ref "C1") (pin "2") (pinfunction "-_2") (pintype "passive"))
      (node (ref "C2") (pin "1") (pinfunction "+_1") (pintype "passive"))
      (node (ref "CB1") (pin "2") (pinfunction "2_2") (pintype "passive"))
      (node (ref "CB10") (pin "2") (pinfunction "2_2") (pintype "passive"))
      (node (ref "CB11") (pin "2") (pinfunction "2_2") (pintype "passive"))
      (node (ref "CB12") (pin "2") (pinfunction "2_2") (pintype "passive"))
      (node (ref "CB13") (pin "2") (pinfunction "2_2") (pintype "passive"))
      (node (ref "CB14") (pin "2") (pinfunction "2_2") (pintype "passive"))
      (node (ref "CB15") (pin "2") (pinfunction "2_2") (pintype "passive"))
      (node (ref "CB16") (pin "2") (pinfunction "2_2") (pintype "passive"))
      (node (ref "CB17") (pin "2") (pinfunction "2_2") (pintype "passive"))
      (node (ref "CB18") (pin "2") (pinfunction "2_2") (pintype "passive"))
      (node (ref "CB19") (pin "2") (pinfunction "2_2") (pintype "passive"))
      (node (ref "CB2") (pin "2") (pinfunction "2_2") (pintype "passive"))
      (node (ref "CB3") (pin "2") (pinfunction "2_2") (pintype "passive"))
      (node (ref "CB4") (pin "2") (pinfunction "2_2") (pintype "passive"))
      (node (ref "CB5") (pin "2") (pinfunction "2_2") (pintype "passive"))
      (node (ref "CB6") (pin "2") (pinfunction "2_2") (pintype "passive"))
      (node (ref "CB7") (pin "2") (pinfunction "2_2") (pintype "passive"))
      (node (ref "CB8") (pin "2") (pinfunction "2_2") (pintype "passive"))
      (node (ref "CB9") (pin "2") (pinfunction "2_2") (pintype "passive"))
      (node (ref "CCLK1") (pin "2") (pinfunction "-_2") (pintype "passive"))
      (node (ref "CCLK2") (pin "2") (pinfunction "-_2") (pintype "passive"))
      (node (ref "CCLK3") (pin "2") (pinfunction "-_2") (pintype "passive"))
      (node (ref "CCLK4") (pin "2") (pinfunction "-_2") (pintype "passive"))
      (node (ref "CCLK5") (pin "2") (pinfunction "-_2") (pintype "passive"))
      (node (ref "CCLK6") (pin "2") (pinfunction "-_2") (pintype "passive"))
      (node (ref "CCO1") (pin "P$3_SLEEVE") (pinfunction "SLEEVE_P$3_SLEEVE") (pintype "passive"))
      (node (ref "CCO2") (pin "P$3_SLEEVE") (pinfunction "SLEEVE_P$3_SLEEVE") (pintype "passive"))
      (node (ref "CCO3") (pin "P$3_SLEEVE") (pinfunction "SLEEVE_P$3_SLEEVE") (pintype "passive"))
      (node (ref "CCO4") (pin "P$3_SLEEVE") (pinfunction "SLEEVE_P$3_SLEEVE") (pintype "passive"))
      (node (ref "CLOCK_IN") (pin "P$3_SLEEVE") (pinfunction "SLEEVE_P$3_SLEEVE") (pintype "passive"))
      (node (ref "COMPLEX1") (pin "P$3_SLEEVE") (pinfunction "SLEEVE_P$3_SLEEVE") (pintype "passive"))
      (node (ref "COMPLEX2") (pin "P$3_SLEEVE") (pinfunction "SLEEVE_P$3_SLEEVE") (pintype "passive"))
      (node (ref "CT1") (pin "2") (pinfunction "2_2") (pintype "passive"))
      (node (ref "CT2") (pin "2") (pinfunction "2_2") (pintype "passive"))
      (node (ref "CT3") (pin "2") (pinfunction "2_2") (pintype "passive"))
      (node (ref "CT4") (pin "2") (pinfunction "2_2") (pintype "passive"))
      (node (ref "CT5") (pin "2") (pinfunction "2_2") (pintype "passive"))
      (node (ref "CT6") (pin "2") (pinfunction "2_2") (pintype "passive"))
      (node (ref "CT7") (pin "2") (pinfunction "2_2") (pintype "passive"))
      (node (ref "CT8") (pin "2") (pinfunction "2_2") (pintype "passive"))
      (node (ref "CTH1") (pin "2") (pinfunction "-_2") (pintype "passive"))
      (node (ref "CTH2") (pin "2") (pinfunction "-_2") (pintype "passive"))
      (node (ref "CTH3") (pin "2") (pinfunction "-_2") (pintype "passive"))
      (node (ref "CTH4") (pin "2") (pinfunction "-_2") (pintype "passive"))
      (node (ref "CTH5") (pin "2") (pinfunction "-_2") (pintype "passive"))
      (node (ref "CTH6") (pin "2") (pinfunction "-_2") (pintype "passive"))
      (node (ref "CTH7") (pin "2") (pinfunction "-_2") (pintype "passive"))
      (node (ref "CTH8") (pin "2") (pinfunction "-_2") (pintype "passive"))
      (node (ref "CV_OUT") (pin "P$3_SLEEVE") (pinfunction "SLEEVE_P$3_SLEEVE") (pintype "passive"))
      (node (ref "IC1") (pin "3") (pinfunction "GND_3") (pintype "passive"))
      (node (ref "IC2") (pin "7") (pinfunction "VSS_7") (pintype "power_in"))
      (node (ref "IC3") (pin "11") (pinfunction "RES_11") (pintype "input"))
      (node (ref "IC3") (pin "8") (pinfunction "VSS_8") (pintype "power_in"))
      (node (ref "IC4") (pin "6") (pinfunction "INH_6") (pintype "input"))
      (node (ref "IC4") (pin "7") (pinfunction "VEE_7") (pintype "power_in"))
      (node (ref "IC4") (pin "8") (pinfunction "GND_8") (pintype "power_in"))
      (node (ref "IC5") (pin "6") (pinfunction "INH_6") (pintype "input"))
      (node (ref "IC5") (pin "7") (pinfunction "VEE_7") (pintype "power_in"))
      (node (ref "IC5") (pin "8") (pinfunction "GND_8") (pintype "power_in"))
      (node (ref "IC6") (pin "14") (pinfunction "GND_14") (pintype "power_in"))
      (node (ref "IC7") (pin "5") (pinfunction "INH_5") (pintype "input"))
      (node (ref "IC7") (pin "8") (pinfunction "VSS_8") (pintype "power_in"))
      (node (ref "IC8") (pin "5") (pinfunction "INH_5") (pintype "input"))
      (node (ref "IC8") (pin "8") (pinfunction "VSS_8") (pintype "power_in"))
      (node (ref "IC9") (pin "7") (pinfunction "VSS_7") (pintype "power_in"))
      (node (ref "LED1") (pin "K") (pinfunction "C_K") (pintype "passive"))
      (node (ref "LED10") (pin "K") (pinfunction "C_K") (pintype "passive"))
      (node (ref "LED11") (pin "K") (pinfunction "C_K") (pintype "passive"))
      (node (ref "LED12") (pin "K") (pinfunction "C_K") (pintype "passive"))
      (node (ref "LED13") (pin "K") (pinfunction "C_K") (pintype "passive"))
      (node (ref "LED14") (pin "K") (pinfunction "C_K") (pintype "passive"))
      (node (ref "LED2") (pin "K") (pinfunction "C_K") (pintype "passive"))
      (node (ref "LED3") (pin "K") (pinfunction "C_K") (pintype "passive"))
      (node (ref "LED4") (pin "K") (pinfunction "C_K") (pintype "passive"))
      (node (ref "LED5") (pin "K") (pinfunction "C_K") (pintype "passive"))
      (node (ref "LED6") (pin "K") (pinfunction "C_K") (pintype "passive"))
      (node (ref "LED7") (pin "K") (pinfunction "C_K") (pintype "passive"))
      (node (ref "LED8") (pin "K") (pinfunction "C_K") (pintype "passive"))
      (node (ref "LED9") (pin "K") (pinfunction "C_K") (pintype "passive"))
      (node (ref "MUX1") (pin "P$3_SLEEVE") (pinfunction "SLEEVE_P$3_SLEEVE") (pintype "passive"))
      (node (ref "MUX2") (pin "P$3_SLEEVE") (pinfunction "SLEEVE_P$3_SLEEVE") (pintype "passive"))
      (node (ref "MUX3") (pin "P$3_SLEEVE") (pinfunction "SLEEVE_P$3_SLEEVE") (pintype "passive"))
      (node (ref "MUX4") (pin "P$3_SLEEVE") (pinfunction "SLEEVE_P$3_SLEEVE") (pintype "passive"))
      (node (ref "MUX5") (pin "P$3_SLEEVE") (pinfunction "SLEEVE_P$3_SLEEVE") (pintype "passive"))
      (node (ref "MUX6") (pin "P$3_SLEEVE") (pinfunction "SLEEVE_P$3_SLEEVE") (pintype "passive"))
      (node (ref "MUX7") (pin "P$3_SLEEVE") (pinfunction "SLEEVE_P$3_SLEEVE") (pintype "passive"))
      (node (ref "MUX8") (pin "P$3_SLEEVE") (pinfunction "SLEEVE_P$3_SLEEVE") (pintype "passive"))
      (node (ref "MUX_OUT") (pin "P$3_SLEEVE") (pinfunction "SLEEVE_P$3_SLEEVE") (pintype "passive"))
      (node (ref "Q1") (pin "P$3_SLEEVE") (pinfunction "SLEEVE_P$3_SLEEVE") (pintype "passive"))
      (node (ref "Q2") (pin "P$3_SLEEVE") (pinfunction "SLEEVE_P$3_SLEEVE") (pintype "passive"))
      (node (ref "Q3") (pin "P$3_SLEEVE") (pinfunction "SLEEVE_P$3_SLEEVE") (pintype "passive"))
      (node (ref "Q4") (pin "P$3_SLEEVE") (pinfunction "SLEEVE_P$3_SLEEVE") (pintype "passive"))
      (node (ref "Q5") (pin "P$3_SLEEVE") (pinfunction "SLEEVE_P$3_SLEEVE") (pintype "passive"))
      (node (ref "Q6") (pin "P$3_SLEEVE") (pinfunction "SLEEVE_P$3_SLEEVE") (pintype "passive"))
      (node (ref "R17") (pin "1") (pinfunction "1_1") (pintype "passive"))
      (node (ref "R18") (pin "1") (pinfunction "1_1") (pintype "passive"))
      (node (ref "U$1") (pin "COM-DOTCOM") (pinfunction "0V_COM-DOTCOM") (pintype "bidirectional"))
      (node (ref "U$1") (pin "COM-EURO1") (pinfunction "0V_COM-EURO1") (pintype "bidirectional"))
      (node (ref "U$1") (pin "COM-EURO2") (pinfunction "0V_COM-EURO2") (pintype "bidirectional"))
      (node (ref "U$1") (pin "COM-EURO3") (pinfunction "0V_COM-EURO3") (pintype "bidirectional"))
      (node (ref "U$1") (pin "COM-EURO4") (pinfunction "0V_COM-EURO4") (pintype "bidirectional"))
      (node (ref "U$1") (pin "COM-EURO5") (pinfunction "0V_COM-EURO5") (pintype "bidirectional"))
      (node (ref "U$1") (pin "COM-EURO6") (pinfunction "0V_COM-EURO6") (pintype "bidirectional"))
      (node (ref "U$1") (pin "COM-MOTM1") (pinfunction "0V_COM-MOTM1") (pintype "bidirectional"))
      (node (ref "U$1") (pin "COM_MOTM2") (pinfunction "0V_COM_MOTM2") (pintype "bidirectional"))
      (node (ref "VCO1") (pin "P$3_SLEEVE") (pinfunction "SLEEVE_P$3_SLEEVE") (pintype "passive"))
      (node (ref "VCO2") (pin "P$3_SLEEVE") (pinfunction "SLEEVE_P$3_SLEEVE") (pintype "passive"))
      (node (ref "VR1") (pin "1") (pinfunction "A_1") (pintype "passive"))
      (node (ref "VR1") (pin "CHASSIS2") (pinfunction "P$1_CHASSIS2") (pintype "passive"))
      (node (ref "VR10") (pin "CHASSIS2") (pinfunction "P$1_CHASSIS2") (pintype "passive"))
      (node (ref "VR11") (pin "CHASSIS2") (pinfunction "P$1_CHASSIS2") (pintype "passive"))
      (node (ref "VR12") (pin "CHASSIS2") (pinfunction "P$1_CHASSIS2") (pintype "passive"))
      (node (ref "VR13") (pin "2") (pinfunction "S_2") (pintype "passive"))
      (node (ref "VR13") (pin "CHASSIS2") (pinfunction "P$1_CHASSIS2") (pintype "passive"))
      (node (ref "VR14") (pin "2") (pinfunction "S_2") (pintype "passive"))
      (node (ref "VR14") (pin "CHASSIS2") (pinfunction "P$1_CHASSIS2") (pintype "passive"))
      (node (ref "VR15") (pin "CHASSIS2") (pinfunction "P$1_CHASSIS2") (pintype "passive"))
      (node (ref "VR2") (pin "1") (pinfunction "A_1") (pintype "passive"))
      (node (ref "VR2") (pin "CHASSIS2") (pinfunction "P$1_CHASSIS2") (pintype "passive"))
      (node (ref "VR3") (pin "1") (pinfunction "A_1") (pintype "passive"))
      (node (ref "VR3") (pin "CHASSIS2") (pinfunction "P$1_CHASSIS2") (pintype "passive"))
      (node (ref "VR4") (pin "1") (pinfunction "A_1") (pintype "passive"))
      (node (ref "VR4") (pin "CHASSIS2") (pinfunction "P$1_CHASSIS2") (pintype "passive"))
      (node (ref "VR5") (pin "1") (pinfunction "A_1") (pintype "passive"))
      (node (ref "VR5") (pin "CHASSIS2") (pinfunction "P$1_CHASSIS2") (pintype "passive"))
      (node (ref "VR6") (pin "1") (pinfunction "A_1") (pintype "passive"))
      (node (ref "VR6") (pin "CHASSIS2") (pinfunction "P$1_CHASSIS2") (pintype "passive"))
      (node (ref "VR7") (pin "1") (pinfunction "A_1") (pintype "passive"))
      (node (ref "VR7") (pin "CHASSIS2") (pinfunction "P$1_CHASSIS2") (pintype "passive"))
      (node (ref "VR8") (pin "1") (pinfunction "A_1") (pintype "passive"))
      (node (ref "VR8") (pin "CHASSIS2") (pinfunction "P$1_CHASSIS2") (pintype "passive"))
      (node (ref "VR9") (pin "CHASSIS2") (pinfunction "P$1_CHASSIS2") (pintype "passive"))
    )
    (net (code "12") (name "Net-(A-SWITCH)") (class "Default")
      (node (ref "A") (pin "P$2_SWITCH") (pinfunction "SWITCH_P$2_SWITCH") (pintype "passive"))
      (node (ref "J1") (pin "1") (pinfunction "1_1") (pintype "passive"))
    )
    (net (code "13") (name "Net-(B-SWITCH)") (class "Default")
      (node (ref "B") (pin "P$2_SWITCH") (pinfunction "SWITCH_P$2_SWITCH") (pintype "passive"))
      (node (ref "J2") (pin "1") (pinfunction "1_1") (pintype "passive"))
    )
    (net (code "14") (name "Net-(C-SWITCH)") (class "Default")
      (node (ref "C") (pin "P$2_SWITCH") (pinfunction "SWITCH_P$2_SWITCH") (pintype "passive"))
      (node (ref "J3") (pin "1") (pinfunction "1_1") (pintype "passive"))
    )
    (net (code "15") (name "Net-(CCLK1-+)") (class "Default")
      (node (ref "CCLK1") (pin "1") (pinfunction "+_1") (pintype "passive"))
      (node (ref "U$2") (pin "2") (pinfunction "X1_2") (pintype "bidirectional"))
    )
    (net (code "16") (name "Net-(CCLK2-+)") (class "Default")
      (node (ref "CCLK2") (pin "1") (pinfunction "+_1") (pintype "passive"))
      (node (ref "U$2") (pin "3") (pinfunction "X2_3") (pintype "bidirectional"))
    )
    (net (code "17") (name "Net-(CCLK3-+)") (class "Default")
      (node (ref "CCLK3") (pin "1") (pinfunction "+_1") (pintype "passive"))
      (node (ref "U$2") (pin "4") (pinfunction "X3_4") (pintype "bidirectional"))
    )
    (net (code "18") (name "Net-(CCLK4-+)") (class "Default")
      (node (ref "CCLK4") (pin "1") (pinfunction "+_1") (pintype "passive"))
      (node (ref "U$2") (pin "5") (pinfunction "X4_5") (pintype "bidirectional"))
    )
    (net (code "19") (name "Net-(CCLK5-+)") (class "Default")
      (node (ref "CCLK5") (pin "1") (pinfunction "+_1") (pintype "passive"))
      (node (ref "U$2") (pin "6") (pinfunction "X5_6") (pintype "bidirectional"))
    )
    (net (code "20") (name "Net-(CCLK6-+)") (class "Default")
      (node (ref "CCLK6") (pin "1") (pinfunction "+_1") (pintype "passive"))
      (node (ref "U$2") (pin "7") (pinfunction "X6_7") (pintype "bidirectional"))
    )
    (net (code "21") (name "Net-(CLOCK_IN-TIP)") (class "Default")
      (node (ref "CLOCK_IN") (pin "P$1_TIP") (pinfunction "TIP_P$1_TIP") (pintype "passive"))
      (node (ref "CLOCK_SELECT") (pin "1") (pinfunction "O_1") (pintype "passive"))
    )
    (net (code "22") (name "Net-(CLOCK_SELECT-P)") (class "Default")
      (node (ref "CLOCK_SELECT") (pin "2") (pinfunction "P_2") (pintype "passive"))
      (node (ref "IC3") (pin "10") (pinfunction "P1_10") (pintype "input"))
    )
    (net (code "23") (name "Net-(CLOCK_SELECT-S)") (class "Default")
      (node (ref "CLOCK_SELECT") (pin "3") (pinfunction "S_3") (pintype "passive"))
      (node (ref "IC2") (pin "2") (pinfunction "O_2") (pintype "output"))
      (node (ref "VR15") (pin "2") (pinfunction "S_2") (pintype "passive"))
    )
    (net (code "24") (name "Net-(CT9-Pad1)") (class "Default")
      (node (ref "CT9") (pin "1") (pinfunction "1_1") (pintype "passive"))
      (node (ref "IC7") (pin "6") (pinfunction "CX_6") (pintype "input"))
    )
    (net (code "25") (name "Net-(CT9-Pad2)") (class "Default")
      (node (ref "CT9") (pin "2") (pinfunction "2_2") (pintype "passive"))
      (node (ref "IC7") (pin "7") (pinfunction "CX_7") (pintype "input"))
    )
    (net (code "26") (name "Net-(CT10-Pad1)") (class "Default")
      (node (ref "CT10") (pin "1") (pinfunction "1_1") (pintype "passive"))
      (node (ref "IC8") (pin "6") (pinfunction "CX_6") (pintype "input"))
    )
    (net (code "27") (name "Net-(CT10-Pad2)") (class "Default")
      (node (ref "CT10") (pin "2") (pinfunction "2_2") (pintype "passive"))
      (node (ref "IC8") (pin "7") (pinfunction "CX_7") (pintype "input"))
    )
    (net (code "28") (name "Net-(CTH1-+)") (class "Default")
      (node (ref "CT1") (pin "1") (pinfunction "1_1") (pintype "passive"))
      (node (ref "CTH1") (pin "1") (pinfunction "+_1") (pintype "passive"))
      (node (ref "SW1") (pin "3") (pinfunction "S_3") (pintype "passive"))
    )
    (net (code "29") (name "Net-(CTH2-+)") (class "Default")
      (node (ref "CT2") (pin "1") (pinfunction "1_1") (pintype "passive"))
      (node (ref "CTH2") (pin "1") (pinfunction "+_1") (pintype "passive"))
      (node (ref "SW1") (pin "1") (pinfunction "O_1") (pintype "passive"))
    )
    (net (code "30") (name "Net-(CTH3-+)") (class "Default")
      (node (ref "CT3") (pin "1") (pinfunction "1_1") (pintype "passive"))
      (node (ref "CTH3") (pin "1") (pinfunction "+_1") (pintype "passive"))
      (node (ref "SW2") (pin "3") (pinfunction "S_3") (pintype "passive"))
    )
    (net (code "31") (name "Net-(CTH4-+)") (class "Default")
      (node (ref "CT4") (pin "1") (pinfunction "1_1") (pintype "passive"))
      (node (ref "CTH4") (pin "1") (pinfunction "+_1") (pintype "passive"))
      (node (ref "SW2") (pin "1") (pinfunction "O_1") (pintype "passive"))
    )
    (net (code "32") (name "Net-(CTH5-+)") (class "Default")
      (node (ref "CT5") (pin "1") (pinfunction "1_1") (pintype "passive"))
      (node (ref "CTH5") (pin "1") (pinfunction "+_1") (pintype "passive"))
      (node (ref "SW3") (pin "3") (pinfunction "S_3") (pintype "passive"))
    )
    (net (code "33") (name "Net-(CTH6-+)") (class "Default")
      (node (ref "CT6") (pin "1") (pinfunction "1_1") (pintype "passive"))
      (node (ref "CTH6") (pin "1") (pinfunction "+_1") (pintype "passive"))
      (node (ref "SW3") (pin "1") (pinfunction "O_1") (pintype "passive"))
    )
    (net (code "34") (name "Net-(CTH7-+)") (class "Default")
      (node (ref "CT7") (pin "1") (pinfunction "1_1") (pintype "passive"))
      (node (ref "CTH7") (pin "1") (pinfunction "+_1") (pintype "passive"))
      (node (ref "SW4") (pin "3") (pinfunction "S_3") (pintype "passive"))
    )
    (net (code "35") (name "Net-(CTH8-+)") (class "Default")
      (node (ref "CT8") (pin "1") (pinfunction "1_1") (pintype "passive"))
      (node (ref "CTH8") (pin "1") (pinfunction "+_1") (pintype "passive"))
      (node (ref "SW4") (pin "1") (pinfunction "O_1") (pintype "passive"))
    )
    (net (code "36") (name "Net-(IC2A-I)") (class "Default")
      (node (ref "IC2") (pin "1") (pinfunction "I_1") (pintype "input"))
      (node (ref "U$2") (pin "1") (pinfunction "COM1_1") (pintype "bidirectional"))
      (node (ref "U$2") (pin "10") (pinfunction "COM2_10") (pintype "bidirectional"))
      (node (ref "VR15") (pin "1") (pinfunction "A_1") (pintype "passive"))
    )
    (net (code "37") (name "Net-(IC2B-I)") (class "Default")
      (node (ref "IC2") (pin "3") (pinfunction "I_3") (pintype "input"))
      (node (ref "SW1") (pin "2") (pinfunction "P_2") (pintype "passive"))
      (node (ref "VR9") (pin "1") (pinfunction "A_1") (pintype "passive"))
    )
    (net (code "38") (name "Net-(IC2B-O)") (class "Default")
      (node (ref "IC2") (pin "4") (pinfunction "O_4") (pintype "output"))
      (node (ref "U1") (pin "3") (pinfunction "+IN_3") (pintype "input"))
      (node (ref "VR9") (pin "2") (pinfunction "S_2") (pintype "passive"))
    )
    (net (code "39") (name "Net-(IC2C-I)") (class "Default")
      (node (ref "IC2") (pin "5") (pinfunction "I_5") (pintype "input"))
      (node (ref "SW2") (pin "2") (pinfunction "P_2") (pintype "passive"))
      (node (ref "VR10") (pin "1") (pinfunction "A_1") (pintype "passive"))
    )
    (net (code "40") (name "Net-(IC2C-O)") (class "Default")
      (node (ref "IC2") (pin "6") (pinfunction "O_6") (pintype "output"))
      (node (ref "U1") (pin "5") (pinfunction "+IN_5") (pintype "input"))
      (node (ref "VR10") (pin "2") (pinfunction "S_2") (pintype "passive"))
    )
    (net (code "41") (name "Net-(IC2D-I)") (class "Default")
      (node (ref "IC2") (pin "9") (pinfunction "I_9") (pintype "input"))
      (node (ref "SW3") (pin "2") (pinfunction "P_2") (pintype "passive"))
      (node (ref "VR11") (pin "1") (pinfunction "A_1") (pintype "passive"))
    )
    (net (code "42") (name "Net-(IC2D-O)") (class "Default")
      (node (ref "IC2") (pin "8") (pinfunction "O_8") (pintype "output"))
      (node (ref "U1") (pin "10") (pinfunction "+IN_10") (pintype "input"))
      (node (ref "VR11") (pin "2") (pinfunction "S_2") (pintype "passive"))
    )
    (net (code "43") (name "Net-(IC2E-I)") (class "Default")
      (node (ref "IC2") (pin "11") (pinfunction "I_11") (pintype "input"))
      (node (ref "SW4") (pin "2") (pinfunction "P_2") (pintype "passive"))
      (node (ref "VR12") (pin "1") (pinfunction "A_1") (pintype "passive"))
    )
    (net (code "44") (name "Net-(IC2E-O)") (class "Default")
      (node (ref "IC2") (pin "10") (pinfunction "O_10") (pintype "output"))
      (node (ref "U1") (pin "12") (pinfunction "+IN_12") (pintype "input"))
      (node (ref "VR12") (pin "2") (pinfunction "S_2") (pintype "passive"))
    )
    (net (code "45") (name "Net-(IC3A-Q1)") (class "Default")
      (node (ref "IC3") (pin "9") (pinfunction "Q1_9") (pintype "output"))
      (node (ref "U3") (pin "10") (pinfunction "+IN_10") (pintype "input"))
    )
    (net (code "46") (name "Net-(IC3A-Q2)") (class "Default")
      (node (ref "IC3") (pin "7") (pinfunction "Q2_7") (pintype "output"))
      (node (ref "U3") (pin "12") (pinfunction "+IN_12") (pintype "input"))
    )
    (net (code "47") (name "Net-(IC3A-Q3)") (class "Default")
      (node (ref "IC3") (pin "6") (pinfunction "Q3_6") (pintype "output"))
      (node (ref "U4") (pin "3") (pinfunction "+IN_3") (pintype "input"))
    )
    (net (code "48") (name "Net-(IC3A-Q4)") (class "Default")
      (node (ref "IC3") (pin "5") (pinfunction "Q4_5") (pintype "output"))
      (node (ref "U4") (pin "5") (pinfunction "+IN_5") (pintype "input"))
    )
    (net (code "49") (name "Net-(IC3A-Q5)") (class "Default")
      (node (ref "IC3") (pin "3") (pinfunction "Q5_3") (pintype "output"))
      (node (ref "U4") (pin "10") (pinfunction "+IN_10") (pintype "input"))
    )
    (net (code "50") (name "Net-(IC3A-Q6)") (class "Default")
      (node (ref "IC3") (pin "2") (pinfunction "Q6_2") (pintype "output"))
      (node (ref "U4") (pin "12") (pinfunction "+IN_12") (pintype "input"))
    )
    (net (code "51") (name "Net-(IC4A-X)") (class "Default")
      (node (ref "IC4") (pin "3") (pinfunction "X_3") (pintype "bidirectional"))
      (node (ref "U2") (pin "10") (pinfunction "+IN_10") (pintype "input"))
    )
    (net (code "52") (name "Net-(IC4A-X0)") (class "Default")
      (node (ref "IC4") (pin "13") (pinfunction "X0_13") (pintype "bidirectional"))
      (node (ref "VR1") (pin "2") (pinfunction "S_2") (pintype "passive"))
    )
    (net (code "53") (name "Net-(IC4A-X1)") (class "Default")
      (node (ref "IC4") (pin "14") (pinfunction "X1_14") (pintype "bidirectional"))
      (node (ref "VR2") (pin "2") (pinfunction "S_2") (pintype "passive"))
    )
    (net (code "54") (name "Net-(IC4A-X2)") (class "Default")
      (node (ref "IC4") (pin "15") (pinfunction "X2_15") (pintype "bidirectional"))
      (node (ref "VR3") (pin "2") (pinfunction "S_2") (pintype "passive"))
    )
    (net (code "55") (name "Net-(IC4A-X3)") (class "Default")
      (node (ref "IC4") (pin "12") (pinfunction "X3_12") (pintype "bidirectional"))
      (node (ref "VR4") (pin "2") (pinfunction "S_2") (pintype "passive"))
    )
    (net (code "56") (name "Net-(IC4A-X4)") (class "Default")
      (node (ref "IC4") (pin "1") (pinfunction "X4_1") (pintype "bidirectional"))
      (node (ref "VR5") (pin "2") (pinfunction "S_2") (pintype "passive"))
    )
    (net (code "57") (name "Net-(IC4A-X5)") (class "Default")
      (node (ref "IC4") (pin "5") (pinfunction "X5_5") (pintype "bidirectional"))
      (node (ref "VR6") (pin "2") (pinfunction "S_2") (pintype "passive"))
    )
    (net (code "58") (name "Net-(IC4A-X6)") (class "Default")
      (node (ref "IC4") (pin "2") (pinfunction "X6_2") (pintype "bidirectional"))
      (node (ref "VR7") (pin "2") (pinfunction "S_2") (pintype "passive"))
    )
    (net (code "59") (name "Net-(IC4A-X7)") (class "Default")
      (node (ref "IC4") (pin "4") (pinfunction "X7_4") (pintype "bidirectional"))
      (node (ref "VR8") (pin "2") (pinfunction "S_2") (pintype "passive"))
    )
    (net (code "60") (name "Net-(IC5A-X0)") (class "Default")
      (node (ref "IC5") (pin "13") (pinfunction "X0_13") (pintype "bidirectional"))
      (node (ref "R1") (pin "1") (pinfunction "1_1") (pintype "passive"))
    )
    (net (code "61") (name "Net-(IC5A-X1)") (class "Default")
      (node (ref "IC5") (pin "14") (pinfunction "X1_14") (pintype "bidirectional"))
      (node (ref "R2") (pin "1") (pinfunction "1_1") (pintype "passive"))
    )
    (net (code "62") (name "Net-(IC5A-X2)") (class "Default")
      (node (ref "IC5") (pin "15") (pinfunction "X2_15") (pintype "bidirectional"))
      (node (ref "R3") (pin "1") (pinfunction "1_1") (pintype "passive"))
    )
    (net (code "63") (name "Net-(IC5A-X3)") (class "Default")
      (node (ref "IC5") (pin "12") (pinfunction "X3_12") (pintype "bidirectional"))
      (node (ref "R4") (pin "1") (pinfunction "1_1") (pintype "passive"))
    )
    (net (code "64") (name "Net-(IC5A-X4)") (class "Default")
      (node (ref "IC5") (pin "1") (pinfunction "X4_1") (pintype "bidirectional"))
      (node (ref "R5") (pin "1") (pinfunction "1_1") (pintype "passive"))
    )
    (net (code "65") (name "Net-(IC5A-X5)") (class "Default")
      (node (ref "IC5") (pin "5") (pinfunction "X5_5") (pintype "bidirectional"))
      (node (ref "R6") (pin "1") (pinfunction "1_1") (pintype "passive"))
    )
    (net (code "66") (name "Net-(IC5A-X6)") (class "Default")
      (node (ref "IC5") (pin "2") (pinfunction "X6_2") (pintype "bidirectional"))
      (node (ref "R7") (pin "1") (pinfunction "1_1") (pintype "passive"))
    )
    (net (code "67") (name "Net-(IC5A-X7)") (class "Default")
      (node (ref "IC5") (pin "4") (pinfunction "X7_4") (pintype "bidirectional"))
      (node (ref "R8") (pin "1") (pinfunction "1_1") (pintype "passive"))
    )
    (net (code "68") (name "Net-(IC6-D)") (class "Default")
      (node (ref "IC6") (pin "8") (pinfunction "D_8") (pintype "passive"))
      (node (ref "U2") (pin "12") (pinfunction "+IN_12") (pintype "input"))
    )
    (net (code "69") (name "Net-(IC6-S1)") (class "Default")
      (node (ref "IC6") (pin "4") (pinfunction "S1_4") (pintype "passive"))
      (node (ref "MUX1") (pin "P$1_TIP") (pinfunction "TIP_P$1_TIP") (pintype "passive"))
    )
    (net (code "70") (name "Net-(IC6-S2)") (class "Default")
      (node (ref "IC6") (pin "5") (pinfunction "S2_5") (pintype "passive"))
      (node (ref "MUX2") (pin "P$1_TIP") (pinfunction "TIP_P$1_TIP") (pintype "passive"))
    )
    (net (code "71") (name "Net-(IC6-S3)") (class "Default")
      (node (ref "IC6") (pin "6") (pinfunction "S3_6") (pintype "passive"))
      (node (ref "MUX3") (pin "P$1_TIP") (pinfunction "TIP_P$1_TIP") (pintype "passive"))
    )
    (net (code "72") (name "Net-(IC6-S4)") (class "Default")
      (node (ref "IC6") (pin "7") (pinfunction "S4_7") (pintype "passive"))
      (node (ref "MUX4") (pin "P$1_TIP") (pinfunction "TIP_P$1_TIP") (pintype "passive"))
    )
    (net (code "73") (name "Net-(IC6-S5)") (class "Default")
      (node (ref "IC6") (pin "12") (pinfunction "S5_12") (pintype "passive"))
      (node (ref "MUX5") (pin "P$1_TIP") (pinfunction "TIP_P$1_TIP") (pintype "passive"))
    )
    (net (code "74") (name "Net-(IC6-S6)") (class "Default")
      (node (ref "IC6") (pin "11") (pinfunction "S6_11") (pintype "passive"))
      (node (ref "MUX6") (pin "P$1_TIP") (pinfunction "TIP_P$1_TIP") (pintype "passive"))
    )
    (net (code "75") (name "Net-(IC6-S7)") (class "Default")
      (node (ref "IC6") (pin "10") (pinfunction "S7_10") (pintype "passive"))
      (node (ref "MUX7") (pin "P$1_TIP") (pinfunction "TIP_P$1_TIP") (pintype "passive"))
    )
    (net (code "76") (name "Net-(IC6-S8)") (class "Default")
      (node (ref "IC6") (pin "9") (pinfunction "S8_9") (pintype "passive"))
      (node (ref "MUX8") (pin "P$1_TIP") (pinfunction "TIP_P$1_TIP") (pintype "passive"))
    )
    (net (code "77") (name "Net-(IC7A-R1)") (class "Default")
      (node (ref "IC7") (pin "11") (pinfunction "R1_11") (pintype "input"))
      (node (ref "R17") (pin "2") (pinfunction "2_2") (pintype "passive"))
    )
    (net (code "78") (name "Net-(IC7A-R2)") (class "Default")
      (node (ref "IC7") (pin "12") (pinfunction "R2_12") (pintype "input"))
      (node (ref "R15") (pin "2") (pinfunction "2_2") (pintype "passive"))
    )
    (net (code "79") (name "Net-(IC7A-VCOOUT)") (class "Default")
      (node (ref "IC7") (pin "4") (pinfunction "VCOOUT_4") (pintype "output"))
      (node (ref "U3") (pin "3") (pinfunction "+IN_3") (pintype "input"))
    )
    (net (code "80") (name "Net-(IC8A-R1)") (class "Default")
      (node (ref "IC8") (pin "11") (pinfunction "R1_11") (pintype "input"))
      (node (ref "R18") (pin "2") (pinfunction "2_2") (pintype "passive"))
    )
    (net (code "81") (name "Net-(IC8A-R2)") (class "Default")
      (node (ref "IC8") (pin "12") (pinfunction "R2_12") (pintype "input"))
      (node (ref "R16") (pin "2") (pinfunction "2_2") (pintype "passive"))
    )
    (net (code "82") (name "Net-(IC8A-VCOOUT)") (class "Default")
      (node (ref "IC8") (pin "4") (pinfunction "VCOOUT_4") (pintype "output"))
      (node (ref "U3") (pin "5") (pinfunction "+IN_5") (pintype "input"))
    )
    (net (code "83") (name "Net-(IC9A-O)") (class "Default")
      (node (ref "IC9") (pin "3") (pinfunction "O_3") (pintype "output"))
      (node (ref "IC9") (pin "5") (pinfunction "I0_5") (pintype "input"))
    )
    (net (code "84") (name "Net-(IC9B-O)") (class "Default")
      (node (ref "IC9") (pin "4") (pinfunction "O_4") (pintype "output"))
      (node (ref "U2") (pin "3") (pinfunction "+IN_3") (pintype "input"))
    )
    (net (code "85") (name "Net-(IC9C-O)") (class "Default")
      (node (ref "IC9") (pin "10") (pinfunction "O_10") (pintype "output"))
      (node (ref "IC9") (pin "12") (pinfunction "I0_12") (pintype "input"))
    )
    (net (code "86") (name "Net-(IC9D-O)") (class "Default")
      (node (ref "IC9") (pin "11") (pinfunction "O_11") (pintype "output"))
      (node (ref "U2") (pin "5") (pinfunction "+IN_5") (pintype "input"))
    )
    (net (code "87") (name "Net-(LED1-PadA)") (class "Default")
      (node (ref "LED1") (pin "A") (pinfunction "A_A") (pintype "passive"))
      (node (ref "R1") (pin "2") (pinfunction "2_2") (pintype "passive"))
    )
    (net (code "88") (name "Net-(LED2-PadA)") (class "Default")
      (node (ref "LED2") (pin "A") (pinfunction "A_A") (pintype "passive"))
      (node (ref "R2") (pin "2") (pinfunction "2_2") (pintype "passive"))
    )
    (net (code "89") (name "Net-(LED3-PadA)") (class "Default")
      (node (ref "LED3") (pin "A") (pinfunction "A_A") (pintype "passive"))
      (node (ref "R3") (pin "2") (pinfunction "2_2") (pintype "passive"))
    )
    (net (code "90") (name "Net-(LED4-PadA)") (class "Default")
      (node (ref "LED4") (pin "A") (pinfunction "A_A") (pintype "passive"))
      (node (ref "R4") (pin "2") (pinfunction "2_2") (pintype "passive"))
    )
    (net (code "91") (name "Net-(LED5-PadA)") (class "Default")
      (node (ref "LED5") (pin "A") (pinfunction "A_A") (pintype "passive"))
      (node (ref "R5") (pin "2") (pinfunction "2_2") (pintype "passive"))
    )
    (net (code "92") (name "Net-(LED6-PadA)") (class "Default")
      (node (ref "LED6") (pin "A") (pinfunction "A_A") (pintype "passive"))
      (node (ref "R6") (pin "2") (pinfunction "2_2") (pintype "passive"))
    )
    (net (code "93") (name "Net-(LED7-PadA)") (class "Default")
      (node (ref "LED7") (pin "A") (pinfunction "A_A") (pintype "passive"))
      (node (ref "R7") (pin "2") (pinfunction "2_2") (pintype "passive"))
    )
    (net (code "94") (name "Net-(LED8-PadA)") (class "Default")
      (node (ref "LED8") (pin "A") (pinfunction "A_A") (pintype "passive"))
      (node (ref "R8") (pin "2") (pinfunction "2_2") (pintype "passive"))
    )
    (net (code "95") (name "Net-(LED9-PadA)") (class "Default")
      (node (ref "LED9") (pin "A") (pinfunction "A_A") (pintype "passive"))
      (node (ref "R9") (pin "2") (pinfunction "2_2") (pintype "passive"))
    )
    (net (code "96") (name "Net-(LED10-PadA)") (class "Default")
      (node (ref "LED10") (pin "A") (pinfunction "A_A") (pintype "passive"))
      (node (ref "R10") (pin "2") (pinfunction "2_2") (pintype "passive"))
    )
    (net (code "97") (name "Net-(LED11-PadA)") (class "Default")
      (node (ref "LED11") (pin "A") (pinfunction "A_A") (pintype "passive"))
      (node (ref "R11") (pin "2") (pinfunction "2_2") (pintype "passive"))
    )
    (net (code "98") (name "Net-(LED12-PadA)") (class "Default")
      (node (ref "LED12") (pin "A") (pinfunction "A_A") (pintype "passive"))
      (node (ref "R12") (pin "2") (pinfunction "2_2") (pintype "passive"))
    )
    (net (code "99") (name "Net-(LED13-PadA)") (class "Default")
      (node (ref "LED13") (pin "A") (pinfunction "A_A") (pintype "passive"))
      (node (ref "R13") (pin "2") (pinfunction "2_2") (pintype "passive"))
    )
    (net (code "100") (name "Net-(LED14-PadA)") (class "Default")
      (node (ref "LED14") (pin "A") (pinfunction "A_A") (pintype "passive"))
      (node (ref "R14") (pin "2") (pinfunction "2_2") (pintype "passive"))
    )
    (net (code "101") (name "Net-(MUX_OUT-TIP)") (class "Default")
      (node (ref "MUX_OUT") (pin "P$1_TIP") (pinfunction "TIP_P$1_TIP") (pintype "passive"))
      (node (ref "U2") (pin "13") (pinfunction "-IN_13") (pintype "input"))
      (node (ref "U2") (pin "14") (pinfunction "OUT_14") (pintype "output"))
    )
    (net (code "102") (name "Net-(VR13-E)") (class "Default")
      (node (ref "R15") (pin "1") (pinfunction "1_1") (pintype "passive"))
      (node (ref "VR13") (pin "3") (pinfunction "E_3") (pintype "passive"))
    )
    (net (code "103") (name "Net-(VR14-E)") (class "Default")
      (node (ref "R16") (pin "1") (pinfunction "1_1") (pintype "passive"))
      (node (ref "VR14") (pin "3") (pinfunction "E_3") (pintype "passive"))
    )
    (net (code "104") (name "Q1BUFFERED") (class "Default")
      (node (ref "J1") (pin "2") (pinfunction "2_2") (pintype "passive"))
      (node (ref "Q1") (pin "P$1_TIP") (pinfunction "TIP_P$1_TIP") (pintype "passive"))
      (node (ref "R9") (pin "1") (pinfunction "1_1") (pintype "passive"))
      (node (ref "U3") (pin "8") (pinfunction "OUT_8") (pintype "output"))
      (node (ref "U3") (pin "9") (pinfunction "-IN_9") (pintype "input"))
    )
    (net (code "105") (name "Q2BUFFERED") (class "Default")
      (node (ref "J2") (pin "2") (pinfunction "2_2") (pintype "passive"))
      (node (ref "Q2") (pin "P$1_TIP") (pinfunction "TIP_P$1_TIP") (pintype "passive"))
      (node (ref "R10") (pin "1") (pinfunction "1_1") (pintype "passive"))
      (node (ref "U3") (pin "13") (pinfunction "-IN_13") (pintype "input"))
      (node (ref "U3") (pin "14") (pinfunction "OUT_14") (pintype "output"))
    )
    (net (code "106") (name "Q3BUFFERED") (class "Default")
      (node (ref "J3") (pin "2") (pinfunction "2_2") (pintype "passive"))
      (node (ref "Q3") (pin "P$1_TIP") (pinfunction "TIP_P$1_TIP") (pintype "passive"))
      (node (ref "R11") (pin "1") (pinfunction "1_1") (pintype "passive"))
      (node (ref "U4") (pin "1") (pinfunction "OUT_1") (pintype "output"))
      (node (ref "U4") (pin "2") (pinfunction "-IN_2") (pintype "input"))
    )
    (net (code "107") (name "Q4BUFFERED") (class "Default")
      (node (ref "Q4") (pin "P$1_TIP") (pinfunction "TIP_P$1_TIP") (pintype "passive"))
      (node (ref "R12") (pin "1") (pinfunction "1_1") (pintype "passive"))
      (node (ref "U4") (pin "6") (pinfunction "-IN_6") (pintype "input"))
      (node (ref "U4") (pin "7") (pinfunction "OUT_7") (pintype "output"))
    )
    (net (code "108") (name "Q5BUFFERED") (class "Default")
      (node (ref "Q5") (pin "P$1_TIP") (pinfunction "TIP_P$1_TIP") (pintype "passive"))
      (node (ref "R13") (pin "1") (pinfunction "1_1") (pintype "passive"))
      (node (ref "U4") (pin "8") (pinfunction "OUT_8") (pintype "output"))
      (node (ref "U4") (pin "9") (pinfunction "-IN_9") (pintype "input"))
    )
    (net (code "109") (name "Q6BUFFERED") (class "Default")
      (node (ref "Q6") (pin "P$1_TIP") (pinfunction "TIP_P$1_TIP") (pintype "passive"))
      (node (ref "R14") (pin "1") (pinfunction "1_1") (pintype "passive"))
      (node (ref "U4") (pin "13") (pinfunction "-IN_13") (pintype "input"))
      (node (ref "U4") (pin "14") (pinfunction "OUT_14") (pintype "output"))
    )
    (net (code "110") (name "V+") (class "Default")
      (node (ref "C1") (pin "1") (pinfunction "+_1") (pintype "passive"))
      (node (ref "CB1") (pin "1") (pinfunction "1_1") (pintype "passive"))
      (node (ref "CB10") (pin "1") (pinfunction "1_1") (pintype "passive"))
      (node (ref "CB12") (pin "1") (pinfunction "1_1") (pintype "passive"))
      (node (ref "CB14") (pin "1") (pinfunction "1_1") (pintype "passive"))
      (node (ref "CB16") (pin "1") (pinfunction "1_1") (pintype "passive"))
      (node (ref "CB18") (pin "1") (pinfunction "1_1") (pintype "passive"))
      (node (ref "IC1") (pin "1") (pinfunction "VI_1") (pintype "input"))
      (node (ref "IC6") (pin "13") (pinfunction "V+_13") (pintype "power_in"))
      (node (ref "IC6") (pin "2") (pinfunction "EN_2") (pintype "input"))
      (node (ref "U$1") (pin "V+DOTCOM") (pinfunction "V+_V+DOTCOM") (pintype "bidirectional"))
      (node (ref "U$1") (pin "V+EURO1") (pinfunction "V+_V+EURO1") (pintype "bidirectional"))
      (node (ref "U$1") (pin "V+EURO2") (pinfunction "V+_V+EURO2") (pintype "bidirectional"))
      (node (ref "U$1") (pin "V+MOTM") (pinfunction "V+_V+MOTM") (pintype "bidirectional"))
      (node (ref "U1") (pin "4") (pinfunction "V+_4") (pintype "power_in"))
      (node (ref "U2") (pin "4") (pinfunction "V+_4") (pintype "power_in"))
      (node (ref "U3") (pin "4") (pinfunction "V+_4") (pintype "power_in"))
      (node (ref "U4") (pin "4") (pinfunction "V+_4") (pintype "power_in"))
    )
    (net (code "111") (name "V-") (class "Default")
      (node (ref "C2") (pin "2") (pinfunction "-_2") (pintype "passive"))
      (node (ref "CB11") (pin "1") (pinfunction "1_1") (pintype "passive"))
      (node (ref "CB13") (pin "1") (pinfunction "1_1") (pintype "passive"))
      (node (ref "CB15") (pin "1") (pinfunction "1_1") (pintype "passive"))
      (node (ref "CB17") (pin "1") (pinfunction "1_1") (pintype "passive"))
      (node (ref "CB19") (pin "1") (pinfunction "1_1") (pintype "passive"))
      (node (ref "IC6") (pin "3") (pinfunction "V-_3") (pintype "power_in"))
      (node (ref "U$1") (pin "V-DOTCOM") (pinfunction "V-_V-DOTCOM") (pintype "bidirectional"))
      (node (ref "U$1") (pin "V-EURO1") (pinfunction "V-_V-EURO1") (pintype "bidirectional"))
      (node (ref "U$1") (pin "V-EURO2") (pinfunction "V-_V-EURO2") (pintype "bidirectional"))
      (node (ref "U$1") (pin "V-MOTM") (pinfunction "V-_V-MOTM") (pintype "bidirectional"))
      (node (ref "U1") (pin "11") (pinfunction "V-_11") (pintype "power_in"))
      (node (ref "U2") (pin "11") (pinfunction "V-_11") (pintype "power_in"))
      (node (ref "U3") (pin "11") (pinfunction "V-_11") (pintype "power_in"))
      (node (ref "U4") (pin "11") (pinfunction "V-_11") (pintype "power_in"))
    )
    (net (code "112") (name "VCC") (class "Default")
      (node (ref "CB2") (pin "1") (pinfunction "1_1") (pintype "passive"))
      (node (ref "CB3") (pin "1") (pinfunction "1_1") (pintype "passive"))
      (node (ref "CB4") (pin "1") (pinfunction "1_1") (pintype "passive"))
      (node (ref "CB5") (pin "1") (pinfunction "1_1") (pintype "passive"))
      (node (ref "CB6") (pin "1") (pinfunction "1_1") (pintype "passive"))
      (node (ref "CB7") (pin "1") (pinfunction "1_1") (pintype "passive"))
      (node (ref "CB8") (pin "1") (pinfunction "1_1") (pintype "passive"))
      (node (ref "CB9") (pin "1") (pinfunction "1_1") (pintype "passive"))
      (node (ref "IC1") (pin "2") (pinfunction "VO_2") (pintype "passive"))
      (node (ref "IC2") (pin "14") (pinfunction "VDD_14") (pintype "power_in"))
      (node (ref "IC3") (pin "16") (pinfunction "VDD_16") (pintype "power_in"))
      (node (ref "IC4") (pin "16") (pinfunction "VCC_16") (pintype "power_in"))
      (node (ref "IC5") (pin "16") (pinfunction "VCC_16") (pintype "power_in"))
      (node (ref "IC5") (pin "3") (pinfunction "X_3") (pintype "bidirectional"))
      (node (ref "IC7") (pin "16") (pinfunction "VDD_16") (pintype "power_in"))
      (node (ref "IC8") (pin "16") (pinfunction "VDD_16") (pintype "power_in"))
      (node (ref "IC9") (pin "14") (pinfunction "VDD_14") (pintype "power_in"))
      (node (ref "VR1") (pin "3") (pinfunction "E_3") (pintype "passive"))
      (node (ref "VR2") (pin "3") (pinfunction "E_3") (pintype "passive"))
      (node (ref "VR3") (pin "3") (pinfunction "E_3") (pintype "passive"))
      (node (ref "VR4") (pin "3") (pinfunction "E_3") (pintype "passive"))
      (node (ref "VR5") (pin "3") (pinfunction "E_3") (pintype "passive"))
      (node (ref "VR6") (pin "3") (pinfunction "E_3") (pintype "passive"))
      (node (ref "VR7") (pin "3") (pinfunction "E_3") (pintype "passive"))
      (node (ref "VR8") (pin "3") (pinfunction "E_3") (pintype "passive"))
    )
    (net (code "113") (name "VCO1_OUT_BUFFERED") (class "Default")
      (node (ref "IC9") (pin "1") (pinfunction "I0_1") (pintype "input"))
      (node (ref "U3") (pin "1") (pinfunction "OUT_1") (pintype "output"))
      (node (ref "U3") (pin "2") (pinfunction "-IN_2") (pintype "input"))
      (node (ref "VCO1") (pin "P$1_TIP") (pinfunction "TIP_P$1_TIP") (pintype "passive"))
    )
    (net (code "114") (name "VCO2_OUT_BUFFERED") (class "Default")
      (node (ref "IC9") (pin "8") (pinfunction "I0_8") (pintype "input"))
      (node (ref "U3") (pin "6") (pinfunction "-IN_6") (pintype "input"))
      (node (ref "U3") (pin "7") (pinfunction "OUT_7") (pintype "output"))
      (node (ref "VCO2") (pin "P$1_TIP") (pinfunction "TIP_P$1_TIP") (pintype "passive"))
    )
    (net (code "115") (name "unconnected-(CCO1-SWITCH-PadP$2_SWITCH)") (class "Default")
      (node (ref "CCO1") (pin "P$2_SWITCH") (pinfunction "SWITCH_P$2_SWITCH") (pintype "passive"))
    )
    (net (code "116") (name "unconnected-(CCO2-SWITCH-PadP$2_SWITCH)") (class "Default")
      (node (ref "CCO2") (pin "P$2_SWITCH") (pinfunction "SWITCH_P$2_SWITCH") (pintype "passive"))
    )
    (net (code "117") (name "unconnected-(CCO3-SWITCH-PadP$2_SWITCH)") (class "Default")
      (node (ref "CCO3") (pin "P$2_SWITCH") (pinfunction "SWITCH_P$2_SWITCH") (pintype "passive"))
    )
    (net (code "118") (name "unconnected-(CCO4-SWITCH-PadP$2_SWITCH)") (class "Default")
      (node (ref "CCO4") (pin "P$2_SWITCH") (pinfunction "SWITCH_P$2_SWITCH") (pintype "passive"))
    )
    (net (code "119") (name "unconnected-(CLOCK_IN-SWITCH-PadP$2_SWITCH)") (class "Default")
      (node (ref "CLOCK_IN") (pin "P$2_SWITCH") (pinfunction "SWITCH_P$2_SWITCH") (pintype "passive"))
    )
    (net (code "120") (name "unconnected-(COMPLEX1-SWITCH-PadP$2_SWITCH)") (class "Default")
      (node (ref "COMPLEX1") (pin "P$2_SWITCH") (pinfunction "SWITCH_P$2_SWITCH") (pintype "passive"))
    )
    (net (code "121") (name "unconnected-(COMPLEX2-SWITCH-PadP$2_SWITCH)") (class "Default")
      (node (ref "COMPLEX2") (pin "P$2_SWITCH") (pinfunction "SWITCH_P$2_SWITCH") (pintype "passive"))
    )
    (net (code "122") (name "unconnected-(CV_OUT-SWITCH-PadP$2_SWITCH)") (class "Default")
      (node (ref "CV_OUT") (pin "P$2_SWITCH") (pinfunction "SWITCH_P$2_SWITCH") (pintype "passive"))
    )
    (net (code "123") (name "unconnected-(IC3A-Q7-Pad4)") (class "Default")
      (node (ref "IC3") (pin "4") (pinfunction "Q7_4") (pintype "output"))
    )
    (net (code "124") (name "unconnected-(IC3A-Q8-Pad13)") (class "Default")
      (node (ref "IC3") (pin "13") (pinfunction "Q8_13") (pintype "output"))
    )
    (net (code "125") (name "unconnected-(IC3A-Q9-Pad12)") (class "Default")
      (node (ref "IC3") (pin "12") (pinfunction "Q9_12") (pintype "output"))
    )
    (net (code "126") (name "unconnected-(IC3A-Q10-Pad14)") (class "Default")
      (node (ref "IC3") (pin "14") (pinfunction "Q10_14") (pintype "output"))
    )
    (net (code "127") (name "unconnected-(IC3A-Q11-Pad15)") (class "Default")
      (node (ref "IC3") (pin "15") (pinfunction "Q11_15") (pintype "output"))
    )
    (net (code "128") (name "unconnected-(IC3A-Q12-Pad1)") (class "Default")
      (node (ref "IC3") (pin "1") (pinfunction "Q12_1") (pintype "output"))
    )
    (net (code "129") (name "unconnected-(IC7A-CIN-Pad3)") (class "Default")
      (node (ref "IC7") (pin "3") (pinfunction "CIN_3") (pintype "input"))
    )
    (net (code "130") (name "unconnected-(IC7A-DEMO-Pad10)") (class "Default")
      (node (ref "IC7") (pin "10") (pinfunction "DEMO_10") (pintype "output"))
    )
    (net (code "131") (name "unconnected-(IC7A-PC1-Pad2)") (class "Default")
      (node (ref "IC7") (pin "2") (pinfunction "PC1_2") (pintype "output"))
    )
    (net (code "132") (name "unconnected-(IC7A-PC2-Pad13)") (class "Default")
      (node (ref "IC7") (pin "13") (pinfunction "PC2_13") (pintype "output"))
    )
    (net (code "133") (name "unconnected-(IC7A-PP-Pad1)") (class "Default")
      (node (ref "IC7") (pin "1") (pinfunction "PP_1") (pintype "output"))
    )
    (net (code "134") (name "unconnected-(IC7A-SIGIN-Pad14)") (class "Default")
      (node (ref "IC7") (pin "14") (pinfunction "SIGIN_14") (pintype "input"))
    )
    (net (code "135") (name "unconnected-(IC7A-ZEN-Pad15)") (class "Default")
      (node (ref "IC7") (pin "15") (pinfunction "ZEN_15") (pintype "input"))
    )
    (net (code "136") (name "unconnected-(IC8A-CIN-Pad3)") (class "Default")
      (node (ref "IC8") (pin "3") (pinfunction "CIN_3") (pintype "input"))
    )
    (net (code "137") (name "unconnected-(IC8A-DEMO-Pad10)") (class "Default")
      (node (ref "IC8") (pin "10") (pinfunction "DEMO_10") (pintype "output"))
    )
    (net (code "138") (name "unconnected-(IC8A-PC1-Pad2)") (class "Default")
      (node (ref "IC8") (pin "2") (pinfunction "PC1_2") (pintype "output"))
    )
    (net (code "139") (name "unconnected-(IC8A-PC2-Pad13)") (class "Default")
      (node (ref "IC8") (pin "13") (pinfunction "PC2_13") (pintype "output"))
    )
    (net (code "140") (name "unconnected-(IC8A-PP-Pad1)") (class "Default")
      (node (ref "IC8") (pin "1") (pinfunction "PP_1") (pintype "output"))
    )
    (net (code "141") (name "unconnected-(IC8A-SIGIN-Pad14)") (class "Default")
      (node (ref "IC8") (pin "14") (pinfunction "SIGIN_14") (pintype "input"))
    )
    (net (code "142") (name "unconnected-(IC8A-ZEN-Pad15)") (class "Default")
      (node (ref "IC8") (pin "15") (pinfunction "ZEN_15") (pintype "input"))
    )
    (net (code "143") (name "unconnected-(MUX1-SWITCH-PadP$2_SWITCH)") (class "Default")
      (node (ref "MUX1") (pin "P$2_SWITCH") (pinfunction "SWITCH_P$2_SWITCH") (pintype "passive"))
    )
    (net (code "144") (name "unconnected-(MUX2-SWITCH-PadP$2_SWITCH)") (class "Default")
      (node (ref "MUX2") (pin "P$2_SWITCH") (pinfunction "SWITCH_P$2_SWITCH") (pintype "passive"))
    )
    (net (code "145") (name "unconnected-(MUX3-SWITCH-PadP$2_SWITCH)") (class "Default")
      (node (ref "MUX3") (pin "P$2_SWITCH") (pinfunction "SWITCH_P$2_SWITCH") (pintype "passive"))
    )
    (net (code "146") (name "unconnected-(MUX4-SWITCH-PadP$2_SWITCH)") (class "Default")
      (node (ref "MUX4") (pin "P$2_SWITCH") (pinfunction "SWITCH_P$2_SWITCH") (pintype "passive"))
    )
    (net (code "147") (name "unconnected-(MUX5-SWITCH-PadP$2_SWITCH)") (class "Default")
      (node (ref "MUX5") (pin "P$2_SWITCH") (pinfunction "SWITCH_P$2_SWITCH") (pintype "passive"))
    )
    (net (code "148") (name "unconnected-(MUX6-SWITCH-PadP$2_SWITCH)") (class "Default")
      (node (ref "MUX6") (pin "P$2_SWITCH") (pinfunction "SWITCH_P$2_SWITCH") (pintype "passive"))
    )
    (net (code "149") (name "unconnected-(MUX7-SWITCH-PadP$2_SWITCH)") (class "Default")
      (node (ref "MUX7") (pin "P$2_SWITCH") (pinfunction "SWITCH_P$2_SWITCH") (pintype "passive"))
    )
    (net (code "150") (name "unconnected-(MUX8-SWITCH-PadP$2_SWITCH)") (class "Default")
      (node (ref "MUX8") (pin "P$2_SWITCH") (pinfunction "SWITCH_P$2_SWITCH") (pintype "passive"))
    )
    (net (code "151") (name "unconnected-(MUX_OUT-SWITCH-PadP$2_SWITCH)") (class "Default")
      (node (ref "MUX_OUT") (pin "P$2_SWITCH") (pinfunction "SWITCH_P$2_SWITCH") (pintype "passive"))
    )
    (net (code "152") (name "unconnected-(Q1-SWITCH-PadP$2_SWITCH)") (class "Default")
      (node (ref "Q1") (pin "P$2_SWITCH") (pinfunction "SWITCH_P$2_SWITCH") (pintype "passive"))
    )
    (net (code "153") (name "unconnected-(Q2-SWITCH-PadP$2_SWITCH)") (class "Default")
      (node (ref "Q2") (pin "P$2_SWITCH") (pinfunction "SWITCH_P$2_SWITCH") (pintype "passive"))
    )
    (net (code "154") (name "unconnected-(Q3-SWITCH-PadP$2_SWITCH)") (class "Default")
      (node (ref "Q3") (pin "P$2_SWITCH") (pinfunction "SWITCH_P$2_SWITCH") (pintype "passive"))
    )
    (net (code "155") (name "unconnected-(Q4-SWITCH-PadP$2_SWITCH)") (class "Default")
      (node (ref "Q4") (pin "P$2_SWITCH") (pinfunction "SWITCH_P$2_SWITCH") (pintype "passive"))
    )
    (net (code "156") (name "unconnected-(Q5-SWITCH-PadP$2_SWITCH)") (class "Default")
      (node (ref "Q5") (pin "P$2_SWITCH") (pinfunction "SWITCH_P$2_SWITCH") (pintype "passive"))
    )
    (net (code "157") (name "unconnected-(Q6-SWITCH-PadP$2_SWITCH)") (class "Default")
      (node (ref "Q6") (pin "P$2_SWITCH") (pinfunction "SWITCH_P$2_SWITCH") (pintype "passive"))
    )
    (net (code "158") (name "unconnected-(U$2-X7-Pad8)") (class "Default")
      (node (ref "U$2") (pin "8") (pinfunction "X7_8") (pintype "bidirectional"))
    )
    (net (code "159") (name "unconnected-(U$2-X8-Pad9)") (class "Default")
      (node (ref "U$2") (pin "9") (pinfunction "X8_9") (pintype "bidirectional"))
    )
    (net (code "160") (name "unconnected-(VCO1-SWITCH-PadP$2_SWITCH)") (class "Default")
      (node (ref "VCO1") (pin "P$2_SWITCH") (pinfunction "SWITCH_P$2_SWITCH") (pintype "passive"))
    )
    (net (code "161") (name "unconnected-(VCO2-SWITCH-PadP$2_SWITCH)") (class "Default")
      (node (ref "VCO2") (pin "P$2_SWITCH") (pinfunction "SWITCH_P$2_SWITCH") (pintype "passive"))
    )
    (net (code "162") (name "unconnected-(VR9-E-Pad3)") (class "Default")
      (node (ref "VR9") (pin "3") (pinfunction "E_3") (pintype "passive"))
    )
    (net (code "163") (name "unconnected-(VR10-E-Pad3)") (class "Default")
      (node (ref "VR10") (pin "3") (pinfunction "E_3") (pintype "passive"))
    )
    (net (code "164") (name "unconnected-(VR11-E-Pad3)") (class "Default")
      (node (ref "VR11") (pin "3") (pinfunction "E_3") (pintype "passive"))
    )
    (net (code "165") (name "unconnected-(VR12-E-Pad3)") (class "Default")
      (node (ref "VR12") (pin "3") (pinfunction "E_3") (pintype "passive"))
    )
    (net (code "166") (name "unconnected-(VR13-A-Pad1)") (class "Default")
      (node (ref "VR13") (pin "1") (pinfunction "A_1") (pintype "passive"))
    )
    (net (code "167") (name "unconnected-(VR14-A-Pad1)") (class "Default")
      (node (ref "VR14") (pin "1") (pinfunction "A_1") (pintype "passive"))
    )
    (net (code "168") (name "unconnected-(VR15-E-Pad3)") (class "Default")
      (node (ref "VR15") (pin "3") (pinfunction "E_3") (pintype "passive"))
    )
  )
)
